# DeMuxRow2.net
KiCad netlist of a schematic drawn in EAGLE
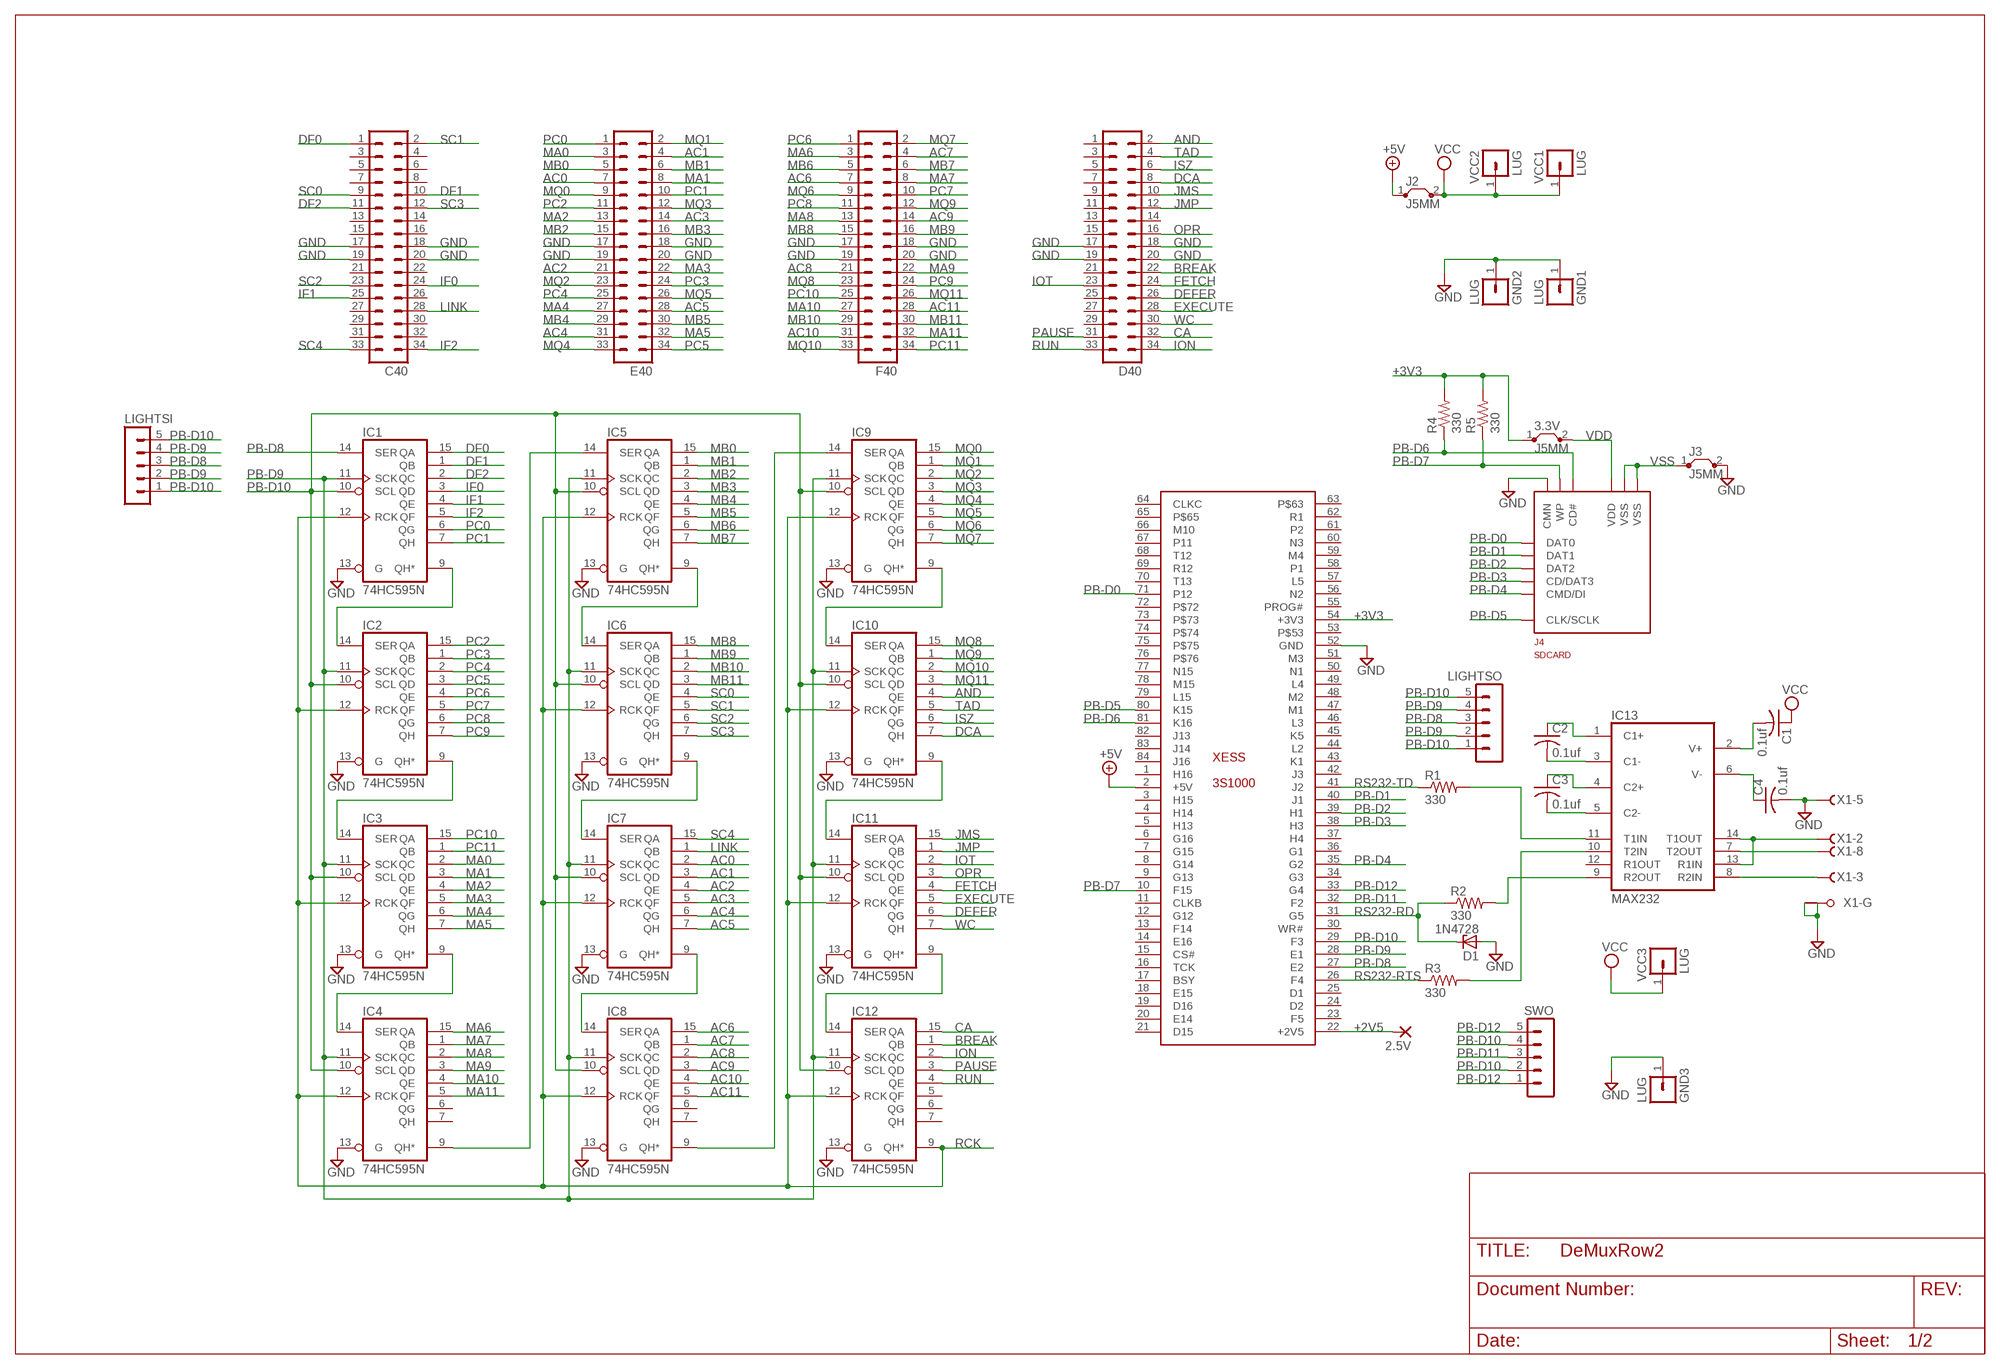
[diagram p0: schematic, sheet 1]
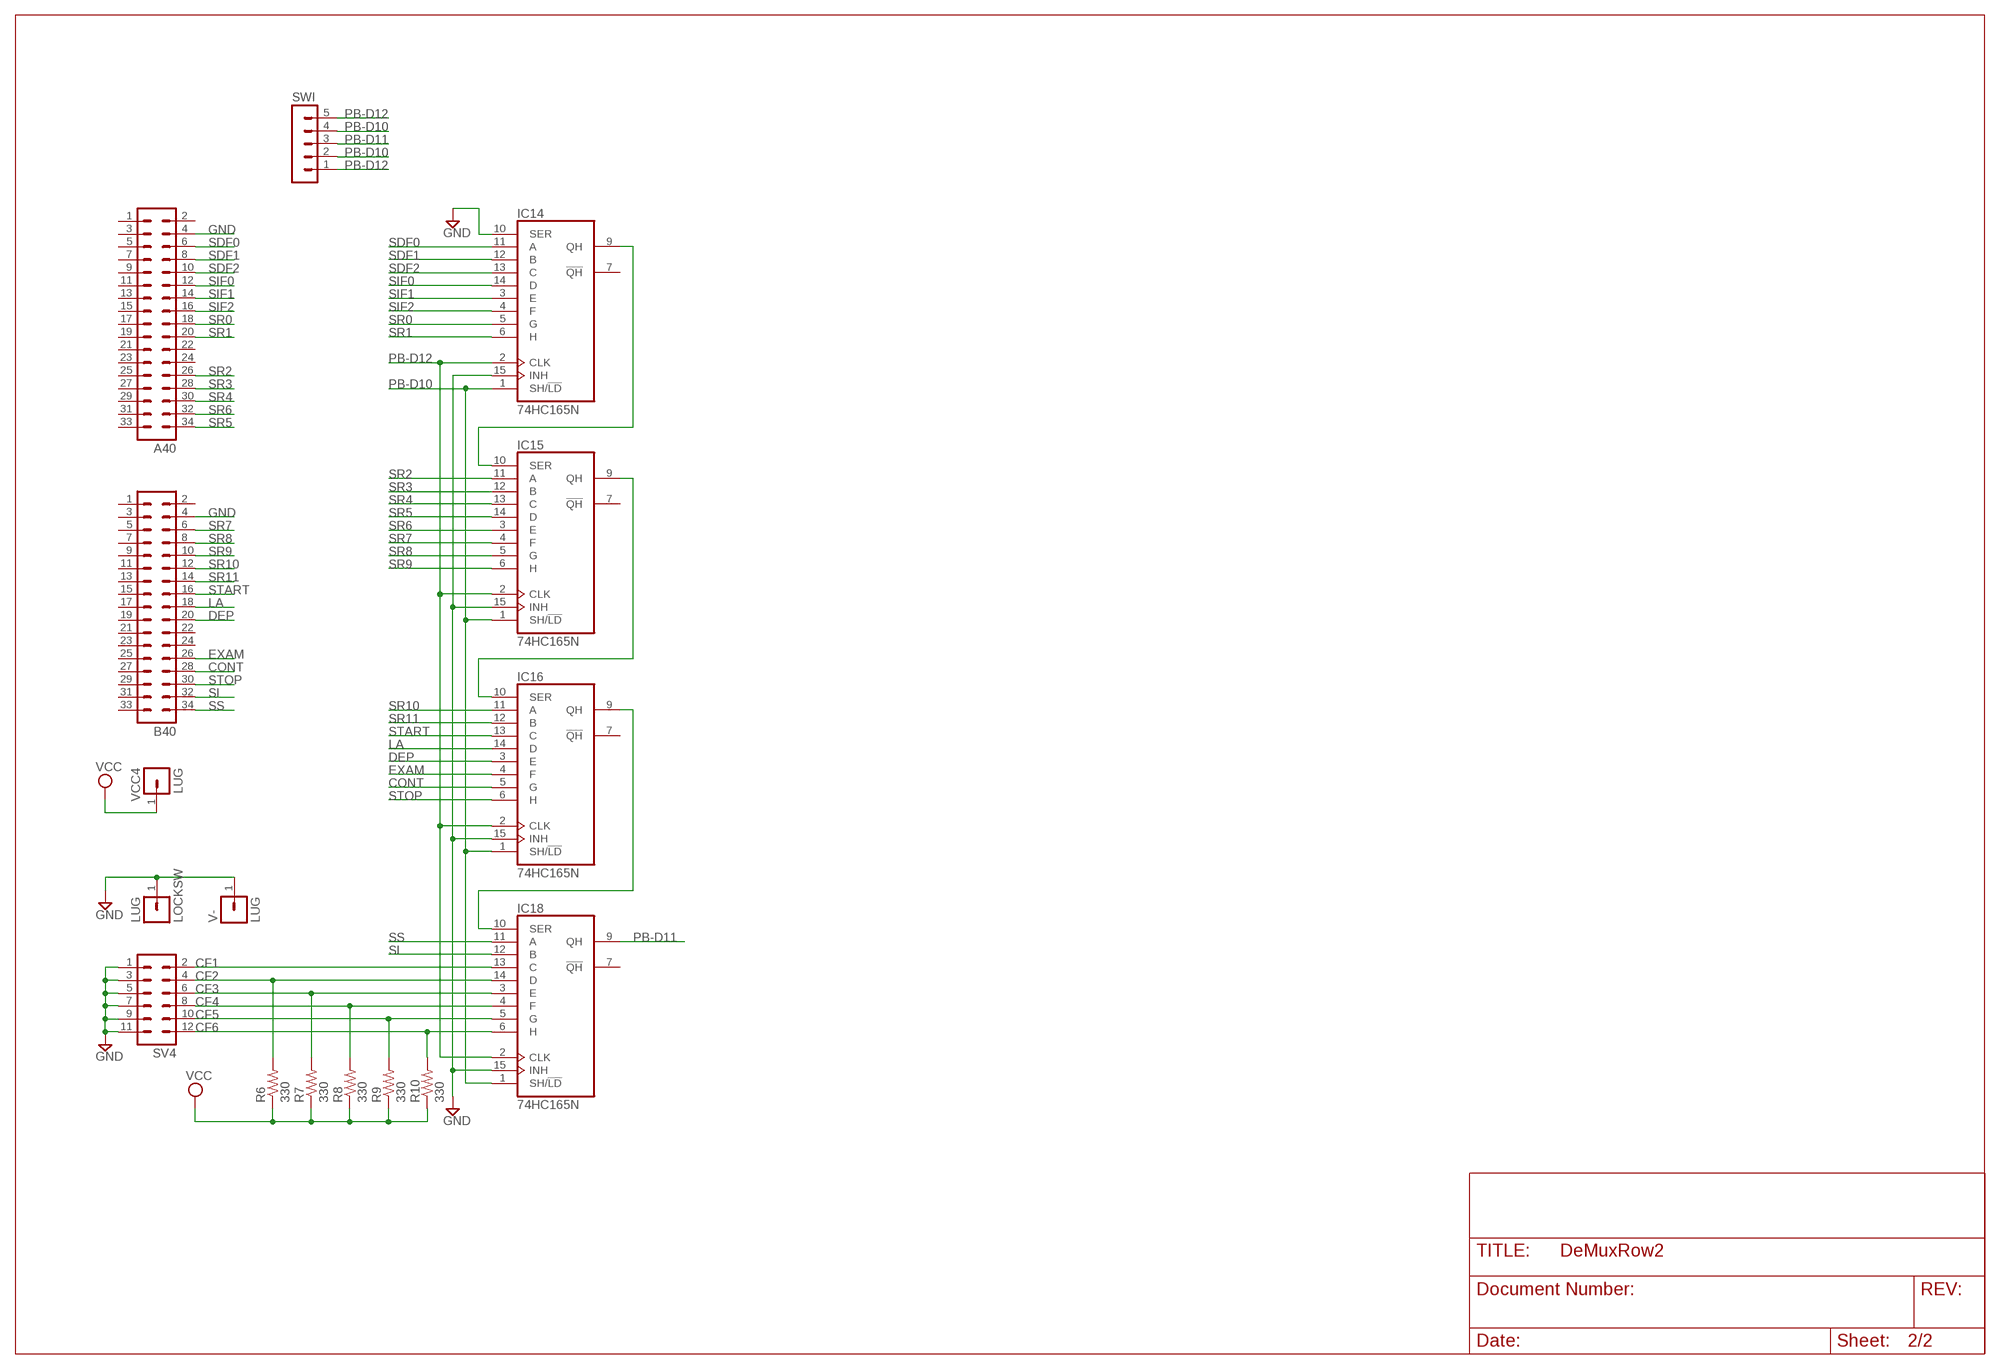
[diagram p1: schematic, sheet 2]

(export (version "E")
  (design (tool "Eeschema 10.0.6"))
  (components
    (comp (ref "A40")
      (value "MA17-2")
      (footprint "eagle-import:MA17-2")
      (libsource (lib "eagle-import") (part "MA17-2"))
    )
    (comp (ref "B40")
      (value "MA17-2")
      (footprint "eagle-import:MA17-2")
      (libsource (lib "eagle-import") (part "MA17-2"))
    )
    (comp (ref "IC14")
      (value "74HC165N")
      (footprint "eagle-import:DIL16")
      (libsource (lib "eagle-import") (part "74165NLS"))
    )
    (comp (ref "IC15")
      (value "74HC165N")
      (footprint "eagle-import:DIL16")
      (libsource (lib "eagle-import") (part "74165NLS"))
    )
    (comp (ref "IC16")
      (value "74HC165N")
      (footprint "eagle-import:DIL16")
      (libsource (lib "eagle-import") (part "74165NLS"))
    )
    (comp (ref "IC18")
      (value "74HC165N")
      (footprint "eagle-import:DIL16")
      (libsource (lib "eagle-import") (part "74165NLS"))
    )
    (comp (ref "LOCKSW")
      (value "LUG")
      (footprint "eagle-import:SPADELUG")
      (libsource (lib "eagle-import") (part "LUG"))
    )
    (comp (ref "R6")
      (value "330")
      (footprint "eagle-import:0207_10")
      (libsource (lib "eagle-import") (part "R-US_0207/10"))
    )
    (comp (ref "R7")
      (value "330")
      (footprint "eagle-import:0207_10")
      (libsource (lib "eagle-import") (part "R-US_0207/10"))
    )
    (comp (ref "R8")
      (value "330")
      (footprint "eagle-import:0207_10")
      (libsource (lib "eagle-import") (part "R-US_0207/10"))
    )
    (comp (ref "R9")
      (value "330")
      (footprint "eagle-import:0207_10")
      (libsource (lib "eagle-import") (part "R-US_0207/10"))
    )
    (comp (ref "R10")
      (value "330")
      (footprint "eagle-import:0207_10")
      (libsource (lib "eagle-import") (part "R-US_0207/10"))
    )
    (comp (ref "SV4")
      (value "MA06-2")
      (footprint "eagle-import:MA06-2")
      (libsource (lib "eagle-import") (part "MA06-2"))
    )
    (comp (ref "SWI")
      (value "MA05-1")
      (footprint "eagle-import:MA05-1")
      (libsource (lib "eagle-import") (part "MA05-1"))
    )
    (comp (ref "V-")
      (value "LUG")
      (footprint "eagle-import:SPADELUG")
      (libsource (lib "eagle-import") (part "LUG"))
    )
    (comp (ref "VCC4")
      (value "LUG")
      (footprint "eagle-import:SPADELUG")
      (libsource (lib "eagle-import") (part "LUG"))
    )
    (comp (ref "2.5V")
      (value "1,6/0,8")
      (footprint "eagle-import:1,6_0,8")
      (libsource (lib "eagle-import") (part "1,6/0,8"))
    )
    (comp (ref "3.3V")
      (value "J5MM")
      (footprint "eagle-import:05")
      (libsource (lib "eagle-import") (part "J5MM"))
    )
    (comp (ref "C1")
      (value "0.1uf")
      (footprint "eagle-import:C050-025X075")
      (libsource (lib "eagle-import") (part "C-US050-025X075"))
    )
    (comp (ref "C2")
      (value "0.1uf")
      (footprint "eagle-import:C050-025X075")
      (libsource (lib "eagle-import") (part "C-US050-025X075"))
    )
    (comp (ref "C3")
      (value "0.1uf")
      (footprint "eagle-import:C050-025X075")
      (libsource (lib "eagle-import") (part "C-US050-025X075"))
    )
    (comp (ref "C4")
      (value "0.1uf")
      (footprint "eagle-import:C050-025X075")
      (libsource (lib "eagle-import") (part "C-US050-025X075"))
    )
    (comp (ref "C40")
      (value "MA17-2")
      (footprint "eagle-import:MA17-2")
      (libsource (lib "eagle-import") (part "MA17-2"))
    )
    (comp (ref "D1")
      (value "1N4728")
      (footprint "eagle-import:DO41Z10")
      (libsource (lib "eagle-import") (part "1N4728"))
    )
    (comp (ref "D40")
      (value "MA17-2")
      (footprint "eagle-import:MA17-2")
      (libsource (lib "eagle-import") (part "MA17-2"))
    )
    (comp (ref "E40")
      (value "MA17-2")
      (footprint "eagle-import:MA17-2")
      (libsource (lib "eagle-import") (part "MA17-2"))
    )
    (comp (ref "F40")
      (value "MA17-2")
      (footprint "eagle-import:MA17-2")
      (libsource (lib "eagle-import") (part "MA17-2"))
    )
    (comp (ref "GND1")
      (value "LUG")
      (footprint "eagle-import:SPADELUG")
      (libsource (lib "eagle-import") (part "LUG"))
    )
    (comp (ref "GND2")
      (value "LUG")
      (footprint "eagle-import:SPADELUG")
      (libsource (lib "eagle-import") (part "LUG"))
    )
    (comp (ref "GND3")
      (value "LUG")
      (footprint "eagle-import:SPADELUG")
      (libsource (lib "eagle-import") (part "LUG"))
    )
    (comp (ref "IC1")
      (value "74HC595N")
      (footprint "eagle-import:DIL16")
      (libsource (lib "eagle-import") (part "74595NLS"))
    )
    (comp (ref "IC2")
      (value "74HC595N")
      (footprint "eagle-import:DIL16")
      (libsource (lib "eagle-import") (part "74595NLS"))
    )
    (comp (ref "IC3")
      (value "74HC595N")
      (footprint "eagle-import:DIL16")
      (libsource (lib "eagle-import") (part "74595NLS"))
    )
    (comp (ref "IC4")
      (value "74HC595N")
      (footprint "eagle-import:DIL16")
      (libsource (lib "eagle-import") (part "74595NLS"))
    )
    (comp (ref "IC5")
      (value "74HC595N")
      (footprint "eagle-import:DIL16")
      (libsource (lib "eagle-import") (part "74595NLS"))
    )
    (comp (ref "IC6")
      (value "74HC595N")
      (footprint "eagle-import:DIL16")
      (libsource (lib "eagle-import") (part "74595NLS"))
    )
    (comp (ref "IC7")
      (value "74HC595N")
      (footprint "eagle-import:DIL16")
      (libsource (lib "eagle-import") (part "74595NLS"))
    )
    (comp (ref "IC8")
      (value "74HC595N")
      (footprint "eagle-import:DIL16")
      (libsource (lib "eagle-import") (part "74595NLS"))
    )
    (comp (ref "IC9")
      (value "74HC595N")
      (footprint "eagle-import:DIL16")
      (libsource (lib "eagle-import") (part "74595NLS"))
    )
    (comp (ref "IC10")
      (value "74HC595N")
      (footprint "eagle-import:DIL16")
      (libsource (lib "eagle-import") (part "74595NLS"))
    )
    (comp (ref "IC11")
      (value "74HC595N")
      (footprint "eagle-import:DIL16")
      (libsource (lib "eagle-import") (part "74595NLS"))
    )
    (comp (ref "IC12")
      (value "74HC595N")
      (footprint "eagle-import:DIL16")
      (libsource (lib "eagle-import") (part "74595NLS"))
    )
    (comp (ref "IC13")
      (value "MAX232")
      (footprint "eagle-import:DIL16")
      (fields (field (name "MF") "MAXIM") (field (name "MPN") "MAX232ACPE+"))
      (libsource (lib "eagle-import") (part "MAX232"))
    )
    (comp (ref "J2")
      (value "J5MM")
      (footprint "eagle-import:05")
      (libsource (lib "eagle-import") (part "J5MM"))
    )
    (comp (ref "J3")
      (value "J5MM")
      (footprint "eagle-import:05")
      (libsource (lib "eagle-import") (part "J5MM"))
    )
    (comp (ref "J4")
      (value "SDCARD")
      (footprint "eagle-import:SCDA5A")
      (libsource (lib "eagle-import") (part "SDCARD"))
    )
    (comp (ref "LIGHTSI")
      (value "MA05-1")
      (footprint "eagle-import:MA05-1")
      (libsource (lib "eagle-import") (part "MA05-1"))
    )
    (comp (ref "LIGHTSO")
      (value "MA05-1")
      (footprint "eagle-import:MA05-1")
      (libsource (lib "eagle-import") (part "MA05-1"))
    )
    (comp (ref "R1")
      (value "330")
      (footprint "eagle-import:0207_10")
      (libsource (lib "eagle-import") (part "R-US_0207/10"))
    )
    (comp (ref "R2")
      (value "330")
      (footprint "eagle-import:0207_10")
      (libsource (lib "eagle-import") (part "R-US_0207/10"))
    )
    (comp (ref "R3")
      (value "330")
      (footprint "eagle-import:0207_10")
      (libsource (lib "eagle-import") (part "R-US_0207/10"))
    )
    (comp (ref "R4")
      (value "330")
      (footprint "eagle-import:0207_10")
      (libsource (lib "eagle-import") (part "R-US_0207/10"))
    )
    (comp (ref "R5")
      (value "330")
      (footprint "eagle-import:0207_10")
      (libsource (lib "eagle-import") (part "R-US_0207/10"))
    )
    (comp (ref "SWO")
      (value "MA05-1")
      (footprint "eagle-import:MA05-1")
      (libsource (lib "eagle-import") (part "MA05-1"))
    )
    (comp (ref "VCC1")
      (value "LUG")
      (footprint "eagle-import:SPADELUG")
      (libsource (lib "eagle-import") (part "LUG"))
    )
    (comp (ref "VCC2")
      (value "LUG")
      (footprint "eagle-import:SPADELUG")
      (libsource (lib "eagle-import") (part "LUG"))
    )
    (comp (ref "VCC3")
      (value "LUG")
      (footprint "eagle-import:SPADELUG")
      (libsource (lib "eagle-import") (part "LUG"))
    )
    (comp (ref "X1")
      (value "F09HPS")
      (footprint "eagle-import:F09HP")
      (libsource (lib "eagle-import") (part "F09HPS"))
    )
    (comp (ref "XESS")
      (value "3S1000")
      (footprint "eagle-import:3S1000")
      (libsource (lib "eagle-import") (part "3S1000"))
    )
  )
  (nets
    (net (code "1") (name "+2V5") (class "Default")
      (node (ref "2.5V") (pin "1") (pinfunction "P_1") (pintype "passive"))
      (node (ref "XESS") (pin "22") (pinfunction "+2V5_22") (pintype "power_in"))
    )
    (net (code "2") (name "+3V3") (class "Default")
      (node (ref "3.3V") (pin "1") (pinfunction "1_1") (pintype "passive"))
      (node (ref "R4") (pin "2") (pinfunction "2_2") (pintype "passive"))
      (node (ref "R5") (pin "2") (pinfunction "2_2") (pintype "passive"))
      (node (ref "XESS") (pin "54") (pinfunction "+3V3_54") (pintype "power_in"))
    )
    (net (code "3") (name "+5V") (class "Default")
      (node (ref "J2") (pin "1") (pinfunction "1_1") (pintype "passive"))
      (node (ref "XESS") (pin "2") (pinfunction "+5V_2") (pintype "power_in"))
    )
    (net (code "4") (name "AC0") (class "Default")
      (node (ref "E40") (pin "7") (pinfunction "7_7") (pintype "passive"))
      (node (ref "IC7") (pin "2") (pinfunction "QC_2") (pintype "tri_state"))
    )
    (net (code "5") (name "AC1") (class "Default")
      (node (ref "E40") (pin "4") (pinfunction "4_4") (pintype "passive"))
      (node (ref "IC7") (pin "3") (pinfunction "QD_3") (pintype "tri_state"))
    )
    (net (code "6") (name "AC2") (class "Default")
      (node (ref "E40") (pin "21") (pinfunction "21_21") (pintype "passive"))
      (node (ref "IC7") (pin "4") (pinfunction "QE_4") (pintype "tri_state"))
    )
    (net (code "7") (name "AC3") (class "Default")
      (node (ref "E40") (pin "14") (pinfunction "14_14") (pintype "passive"))
      (node (ref "IC7") (pin "5") (pinfunction "QF_5") (pintype "tri_state"))
    )
    (net (code "8") (name "AC4") (class "Default")
      (node (ref "E40") (pin "31") (pinfunction "31_31") (pintype "passive"))
      (node (ref "IC7") (pin "6") (pinfunction "QG_6") (pintype "tri_state"))
    )
    (net (code "9") (name "AC5") (class "Default")
      (node (ref "E40") (pin "28") (pinfunction "28_28") (pintype "passive"))
      (node (ref "IC7") (pin "7") (pinfunction "QH_7") (pintype "tri_state"))
    )
    (net (code "10") (name "AC6") (class "Default")
      (node (ref "F40") (pin "7") (pinfunction "7_7") (pintype "passive"))
      (node (ref "IC8") (pin "15") (pinfunction "QA_15") (pintype "tri_state"))
    )
    (net (code "11") (name "AC7") (class "Default")
      (node (ref "F40") (pin "4") (pinfunction "4_4") (pintype "passive"))
      (node (ref "IC8") (pin "1") (pinfunction "QB_1") (pintype "tri_state"))
    )
    (net (code "12") (name "AC8") (class "Default")
      (node (ref "F40") (pin "21") (pinfunction "21_21") (pintype "passive"))
      (node (ref "IC8") (pin "2") (pinfunction "QC_2") (pintype "tri_state"))
    )
    (net (code "13") (name "AC9") (class "Default")
      (node (ref "F40") (pin "14") (pinfunction "14_14") (pintype "passive"))
      (node (ref "IC8") (pin "3") (pinfunction "QD_3") (pintype "tri_state"))
    )
    (net (code "14") (name "AC10") (class "Default")
      (node (ref "F40") (pin "31") (pinfunction "31_31") (pintype "passive"))
      (node (ref "IC8") (pin "4") (pinfunction "QE_4") (pintype "tri_state"))
    )
    (net (code "15") (name "AC11") (class "Default")
      (node (ref "F40") (pin "28") (pinfunction "28_28") (pintype "passive"))
      (node (ref "IC8") (pin "5") (pinfunction "QF_5") (pintype "tri_state"))
    )
    (net (code "16") (name "AND") (class "Default")
      (node (ref "D40") (pin "2") (pinfunction "2_2") (pintype "passive"))
      (node (ref "IC10") (pin "4") (pinfunction "QE_4") (pintype "tri_state"))
    )
    (net (code "17") (name "BREAK") (class "Default")
      (node (ref "D40") (pin "22") (pinfunction "22_22") (pintype "passive"))
      (node (ref "IC12") (pin "1") (pinfunction "QB_1") (pintype "tri_state"))
    )
    (net (code "18") (name "CA") (class "Default")
      (node (ref "D40") (pin "32") (pinfunction "32_32") (pintype "passive"))
      (node (ref "IC12") (pin "15") (pinfunction "QA_15") (pintype "tri_state"))
    )
    (net (code "19") (name "CF1") (class "Default")
      (node (ref "IC18") (pin "13") (pinfunction "C_13") (pintype "input"))
      (node (ref "SV4") (pin "2") (pinfunction "2_2") (pintype "passive"))
    )
    (net (code "20") (name "CF2") (class "Default")
      (node (ref "IC18") (pin "14") (pinfunction "D_14") (pintype "input"))
      (node (ref "R6") (pin "2") (pinfunction "2_2") (pintype "passive"))
      (node (ref "SV4") (pin "4") (pinfunction "4_4") (pintype "passive"))
    )
    (net (code "21") (name "CF3") (class "Default")
      (node (ref "IC18") (pin "3") (pinfunction "E_3") (pintype "input"))
      (node (ref "R7") (pin "2") (pinfunction "2_2") (pintype "passive"))
      (node (ref "SV4") (pin "6") (pinfunction "6_6") (pintype "passive"))
    )
    (net (code "22") (name "CF4") (class "Default")
      (node (ref "IC18") (pin "4") (pinfunction "F_4") (pintype "input"))
      (node (ref "R8") (pin "2") (pinfunction "2_2") (pintype "passive"))
      (node (ref "SV4") (pin "8") (pinfunction "8_8") (pintype "passive"))
    )
    (net (code "23") (name "CF5") (class "Default")
      (node (ref "IC18") (pin "5") (pinfunction "G_5") (pintype "input"))
      (node (ref "R9") (pin "2") (pinfunction "2_2") (pintype "passive"))
      (node (ref "SV4") (pin "10") (pinfunction "10_10") (pintype "passive"))
    )
    (net (code "24") (name "CF6") (class "Default")
      (node (ref "IC18") (pin "6") (pinfunction "H_6") (pintype "input"))
      (node (ref "R10") (pin "2") (pinfunction "2_2") (pintype "passive"))
      (node (ref "SV4") (pin "12") (pinfunction "12_12") (pintype "passive"))
    )
    (net (code "25") (name "CONT") (class "Default")
      (node (ref "B40") (pin "28") (pinfunction "28_28") (pintype "passive"))
      (node (ref "IC16") (pin "5") (pinfunction "G_5") (pintype "input"))
    )
    (net (code "26") (name "DCA") (class "Default")
      (node (ref "D40") (pin "8") (pinfunction "8_8") (pintype "passive"))
      (node (ref "IC10") (pin "7") (pinfunction "QH_7") (pintype "tri_state"))
    )
    (net (code "27") (name "DEFER") (class "Default")
      (node (ref "D40") (pin "26") (pinfunction "26_26") (pintype "passive"))
      (node (ref "IC11") (pin "6") (pinfunction "QG_6") (pintype "tri_state"))
    )
    (net (code "28") (name "DEP") (class "Default")
      (node (ref "B40") (pin "20") (pinfunction "20_20") (pintype "passive"))
      (node (ref "IC16") (pin "3") (pinfunction "E_3") (pintype "input"))
    )
    (net (code "29") (name "DF0") (class "Default")
      (node (ref "C40") (pin "1") (pinfunction "1_1") (pintype "passive"))
      (node (ref "IC1") (pin "15") (pinfunction "QA_15") (pintype "tri_state"))
    )
    (net (code "30") (name "DF1") (class "Default")
      (node (ref "C40") (pin "10") (pinfunction "10_10") (pintype "passive"))
      (node (ref "IC1") (pin "1") (pinfunction "QB_1") (pintype "tri_state"))
    )
    (net (code "31") (name "DF2") (class "Default")
      (node (ref "C40") (pin "11") (pinfunction "11_11") (pintype "passive"))
      (node (ref "IC1") (pin "2") (pinfunction "QC_2") (pintype "tri_state"))
    )
    (net (code "32") (name "EXAM") (class "Default")
      (node (ref "B40") (pin "26") (pinfunction "26_26") (pintype "passive"))
      (node (ref "IC16") (pin "4") (pinfunction "F_4") (pintype "input"))
    )
    (net (code "33") (name "EXECUTE") (class "Default")
      (node (ref "D40") (pin "28") (pinfunction "28_28") (pintype "passive"))
      (node (ref "IC11") (pin "5") (pinfunction "QF_5") (pintype "tri_state"))
    )
    (net (code "34") (name "FETCH") (class "Default")
      (node (ref "D40") (pin "24") (pinfunction "24_24") (pintype "passive"))
      (node (ref "IC11") (pin "4") (pinfunction "QE_4") (pintype "tri_state"))
    )
    (net (code "35") (name "GND") (class "Default")
      (node (ref "A40") (pin "4") (pinfunction "4_4") (pintype "passive"))
      (node (ref "B40") (pin "4") (pinfunction "4_4") (pintype "passive"))
      (node (ref "C4") (pin "2") (pinfunction "2_2") (pintype "passive"))
      (node (ref "C40") (pin "17") (pinfunction "17_17") (pintype "passive"))
      (node (ref "C40") (pin "18") (pinfunction "18_18") (pintype "passive"))
      (node (ref "C40") (pin "19") (pinfunction "19_19") (pintype "passive"))
      (node (ref "C40") (pin "20") (pinfunction "20_20") (pintype "passive"))
      (node (ref "D1") (pin "A") (pinfunction "A_A") (pintype "passive"))
      (node (ref "D40") (pin "17") (pinfunction "17_17") (pintype "passive"))
      (node (ref "D40") (pin "18") (pinfunction "18_18") (pintype "passive"))
      (node (ref "D40") (pin "19") (pinfunction "19_19") (pintype "passive"))
      (node (ref "D40") (pin "20") (pinfunction "20_20") (pintype "passive"))
      (node (ref "E40") (pin "17") (pinfunction "17_17") (pintype "passive"))
      (node (ref "E40") (pin "18") (pinfunction "18_18") (pintype "passive"))
      (node (ref "E40") (pin "19") (pinfunction "19_19") (pintype "passive"))
      (node (ref "E40") (pin "20") (pinfunction "20_20") (pintype "passive"))
      (node (ref "F40") (pin "17") (pinfunction "17_17") (pintype "passive"))
      (node (ref "F40") (pin "18") (pinfunction "18_18") (pintype "passive"))
      (node (ref "F40") (pin "19") (pinfunction "19_19") (pintype "passive"))
      (node (ref "F40") (pin "20") (pinfunction "20_20") (pintype "passive"))
      (node (ref "GND1") (pin "1") (pinfunction "1_1") (pintype "passive"))
      (node (ref "GND2") (pin "1") (pinfunction "1_1") (pintype "passive"))
      (node (ref "GND3") (pin "1") (pinfunction "1_1") (pintype "passive"))
      (node (ref "IC1") (pin "13") (pinfunction "G_13") (pintype "input"))
      (node (ref "IC10") (pin "13") (pinfunction "G_13") (pintype "input"))
      (node (ref "IC11") (pin "13") (pinfunction "G_13") (pintype "input"))
      (node (ref "IC12") (pin "13") (pinfunction "G_13") (pintype "input"))
      (node (ref "IC14") (pin "10") (pinfunction "SER_10") (pintype "input"))
      (node (ref "IC14") (pin "15") (pinfunction "INH_15") (pintype "input"))
      (node (ref "IC15") (pin "15") (pinfunction "INH_15") (pintype "input"))
      (node (ref "IC16") (pin "15") (pinfunction "INH_15") (pintype "input"))
      (node (ref "IC18") (pin "15") (pinfunction "INH_15") (pintype "input"))
      (node (ref "IC2") (pin "13") (pinfunction "G_13") (pintype "input"))
      (node (ref "IC3") (pin "13") (pinfunction "G_13") (pintype "input"))
      (node (ref "IC4") (pin "13") (pinfunction "G_13") (pintype "input"))
      (node (ref "IC5") (pin "13") (pinfunction "G_13") (pintype "input"))
      (node (ref "IC6") (pin "13") (pinfunction "G_13") (pintype "input"))
      (node (ref "IC7") (pin "13") (pinfunction "G_13") (pintype "input"))
      (node (ref "IC8") (pin "13") (pinfunction "G_13") (pintype "input"))
      (node (ref "IC9") (pin "13") (pinfunction "G_13") (pintype "input"))
      (node (ref "J3") (pin "2") (pinfunction "2_2") (pintype "passive"))
      (node (ref "J4") (pin "11") (pinfunction "CMN_11") (pintype "input"))
      (node (ref "LOCKSW") (pin "1") (pinfunction "1_1") (pintype "passive"))
      (node (ref "SV4") (pin "1") (pinfunction "1_1") (pintype "passive"))
      (node (ref "SV4") (pin "11") (pinfunction "11_11") (pintype "passive"))
      (node (ref "SV4") (pin "3") (pinfunction "3_3") (pintype "passive"))
      (node (ref "SV4") (pin "5") (pinfunction "5_5") (pintype "passive"))
      (node (ref "SV4") (pin "7") (pinfunction "7_7") (pintype "passive"))
      (node (ref "SV4") (pin "9") (pinfunction "9_9") (pintype "passive"))
      (node (ref "V-") (pin "1") (pinfunction "1_1") (pintype "passive"))
      (node (ref "X1") (pin "5") (pinfunction "F_5") (pintype "passive"))
      (node (ref "X1") (pin "G1") (pinfunction "G1_G1") (pintype "passive"))
      (node (ref "X1") (pin "G2") (pinfunction "G2_G2") (pintype "passive"))
      (node (ref "XESS") (pin "52") (pinfunction "GND_52") (pintype "power_in"))
    )
    (net (code "36") (name "IF0") (class "Default")
      (node (ref "C40") (pin "24") (pinfunction "24_24") (pintype "passive"))
      (node (ref "IC1") (pin "3") (pinfunction "QD_3") (pintype "tri_state"))
    )
    (net (code "37") (name "IF1") (class "Default")
      (node (ref "C40") (pin "25") (pinfunction "25_25") (pintype "passive"))
      (node (ref "IC1") (pin "4") (pinfunction "QE_4") (pintype "tri_state"))
    )
    (net (code "38") (name "IF2") (class "Default")
      (node (ref "C40") (pin "34") (pinfunction "34_34") (pintype "passive"))
      (node (ref "IC1") (pin "5") (pinfunction "QF_5") (pintype "tri_state"))
    )
    (net (code "39") (name "ION") (class "Default")
      (node (ref "D40") (pin "34") (pinfunction "34_34") (pintype "passive"))
      (node (ref "IC12") (pin "2") (pinfunction "QC_2") (pintype "tri_state"))
    )
    (net (code "40") (name "IOT") (class "Default")
      (node (ref "D40") (pin "23") (pinfunction "23_23") (pintype "passive"))
      (node (ref "IC11") (pin "2") (pinfunction "QC_2") (pintype "tri_state"))
    )
    (net (code "41") (name "ISZ") (class "Default")
      (node (ref "D40") (pin "6") (pinfunction "6_6") (pintype "passive"))
      (node (ref "IC10") (pin "6") (pinfunction "QG_6") (pintype "tri_state"))
    )
    (net (code "42") (name "JMP") (class "Default")
      (node (ref "D40") (pin "12") (pinfunction "12_12") (pintype "passive"))
      (node (ref "IC11") (pin "1") (pinfunction "QB_1") (pintype "tri_state"))
    )
    (net (code "43") (name "JMS") (class "Default")
      (node (ref "D40") (pin "10") (pinfunction "10_10") (pintype "passive"))
      (node (ref "IC11") (pin "15") (pinfunction "QA_15") (pintype "tri_state"))
    )
    (net (code "44") (name "LA") (class "Default")
      (node (ref "B40") (pin "18") (pinfunction "18_18") (pintype "passive"))
      (node (ref "IC16") (pin "14") (pinfunction "D_14") (pintype "input"))
    )
    (net (code "45") (name "LINK") (class "Default")
      (node (ref "C40") (pin "28") (pinfunction "28_28") (pintype "passive"))
      (node (ref "IC7") (pin "1") (pinfunction "QB_1") (pintype "tri_state"))
    )
    (net (code "46") (name "MA0") (class "Default")
      (node (ref "E40") (pin "3") (pinfunction "3_3") (pintype "passive"))
      (node (ref "IC3") (pin "2") (pinfunction "QC_2") (pintype "tri_state"))
    )
    (net (code "47") (name "MA1") (class "Default")
      (node (ref "E40") (pin "8") (pinfunction "8_8") (pintype "passive"))
      (node (ref "IC3") (pin "3") (pinfunction "QD_3") (pintype "tri_state"))
    )
    (net (code "48") (name "MA2") (class "Default")
      (node (ref "E40") (pin "13") (pinfunction "13_13") (pintype "passive"))
      (node (ref "IC3") (pin "4") (pinfunction "QE_4") (pintype "tri_state"))
    )
    (net (code "49") (name "MA3") (class "Default")
      (node (ref "E40") (pin "22") (pinfunction "22_22") (pintype "passive"))
      (node (ref "IC3") (pin "5") (pinfunction "QF_5") (pintype "tri_state"))
    )
    (net (code "50") (name "MA4") (class "Default")
      (node (ref "E40") (pin "27") (pinfunction "27_27") (pintype "passive"))
      (node (ref "IC3") (pin "6") (pinfunction "QG_6") (pintype "tri_state"))
    )
    (net (code "51") (name "MA5") (class "Default")
      (node (ref "E40") (pin "32") (pinfunction "32_32") (pintype "passive"))
      (node (ref "IC3") (pin "7") (pinfunction "QH_7") (pintype "tri_state"))
    )
    (net (code "52") (name "MA6") (class "Default")
      (node (ref "F40") (pin "3") (pinfunction "3_3") (pintype "passive"))
      (node (ref "IC4") (pin "15") (pinfunction "QA_15") (pintype "tri_state"))
    )
    (net (code "53") (name "MA7") (class "Default")
      (node (ref "F40") (pin "8") (pinfunction "8_8") (pintype "passive"))
      (node (ref "IC4") (pin "1") (pinfunction "QB_1") (pintype "tri_state"))
    )
    (net (code "54") (name "MA8") (class "Default")
      (node (ref "F40") (pin "13") (pinfunction "13_13") (pintype "passive"))
      (node (ref "IC4") (pin "2") (pinfunction "QC_2") (pintype "tri_state"))
    )
    (net (code "55") (name "MA9") (class "Default")
      (node (ref "F40") (pin "22") (pinfunction "22_22") (pintype "passive"))
      (node (ref "IC4") (pin "3") (pinfunction "QD_3") (pintype "tri_state"))
    )
    (net (code "56") (name "MA10") (class "Default")
      (node (ref "F40") (pin "27") (pinfunction "27_27") (pintype "passive"))
      (node (ref "IC4") (pin "4") (pinfunction "QE_4") (pintype "tri_state"))
    )
    (net (code "57") (name "MA11") (class "Default")
      (node (ref "F40") (pin "32") (pinfunction "32_32") (pintype "passive"))
      (node (ref "IC4") (pin "5") (pinfunction "QF_5") (pintype "tri_state"))
    )
    (net (code "58") (name "MB0") (class "Default")
      (node (ref "E40") (pin "5") (pinfunction "5_5") (pintype "passive"))
      (node (ref "IC5") (pin "15") (pinfunction "QA_15") (pintype "tri_state"))
    )
    (net (code "59") (name "MB1") (class "Default")
      (node (ref "E40") (pin "6") (pinfunction "6_6") (pintype "passive"))
      (node (ref "IC5") (pin "1") (pinfunction "QB_1") (pintype "tri_state"))
    )
    (net (code "60") (name "MB2") (class "Default")
      (node (ref "E40") (pin "15") (pinfunction "15_15") (pintype "passive"))
      (node (ref "IC5") (pin "2") (pinfunction "QC_2") (pintype "tri_state"))
    )
    (net (code "61") (name "MB3") (class "Default")
      (node (ref "E40") (pin "16") (pinfunction "16_16") (pintype "passive"))
      (node (ref "IC5") (pin "3") (pinfunction "QD_3") (pintype "tri_state"))
    )
    (net (code "62") (name "MB4") (class "Default")
      (node (ref "E40") (pin "29") (pinfunction "29_29") (pintype "passive"))
      (node (ref "IC5") (pin "4") (pinfunction "QE_4") (pintype "tri_state"))
    )
    (net (code "63") (name "MB5") (class "Default")
      (node (ref "E40") (pin "30") (pinfunction "30_30") (pintype "passive"))
      (node (ref "IC5") (pin "5") (pinfunction "QF_5") (pintype "tri_state"))
    )
    (net (code "64") (name "MB6") (class "Default")
      (node (ref "F40") (pin "5") (pinfunction "5_5") (pintype "passive"))
      (node (ref "IC5") (pin "6") (pinfunction "QG_6") (pintype "tri_state"))
    )
    (net (code "65") (name "MB7") (class "Default")
      (node (ref "F40") (pin "6") (pinfunction "6_6") (pintype "passive"))
      (node (ref "IC5") (pin "7") (pinfunction "QH_7") (pintype "tri_state"))
    )
    (net (code "66") (name "MB8") (class "Default")
      (node (ref "F40") (pin "15") (pinfunction "15_15") (pintype "passive"))
      (node (ref "IC6") (pin "15") (pinfunction "QA_15") (pintype "tri_state"))
    )
    (net (code "67") (name "MB9") (class "Default")
      (node (ref "F40") (pin "16") (pinfunction "16_16") (pintype "passive"))
      (node (ref "IC6") (pin "1") (pinfunction "QB_1") (pintype "tri_state"))
    )
    (net (code "68") (name "MB10") (class "Default")
      (node (ref "F40") (pin "29") (pinfunction "29_29") (pintype "passive"))
      (node (ref "IC6") (pin "2") (pinfunction "QC_2") (pintype "tri_state"))
    )
    (net (code "69") (name "MB11") (class "Default")
      (node (ref "F40") (pin "30") (pinfunction "30_30") (pintype "passive"))
      (node (ref "IC6") (pin "3") (pinfunction "QD_3") (pintype "tri_state"))
    )
    (net (code "70") (name "MQ0") (class "Default")
      (node (ref "E40") (pin "9") (pinfunction "9_9") (pintype "passive"))
      (node (ref "IC9") (pin "15") (pinfunction "QA_15") (pintype "tri_state"))
    )
    (net (code "71") (name "MQ1") (class "Default")
      (node (ref "E40") (pin "2") (pinfunction "2_2") (pintype "passive"))
      (node (ref "IC9") (pin "1") (pinfunction "QB_1") (pintype "tri_state"))
    )
    (net (code "72") (name "MQ2") (class "Default")
      (node (ref "E40") (pin "23") (pinfunction "23_23") (pintype "passive"))
      (node (ref "IC9") (pin "2") (pinfunction "QC_2") (pintype "tri_state"))
    )
    (net (code "73") (name "MQ3") (class "Default")
      (node (ref "E40") (pin "12") (pinfunction "12_12") (pintype "passive"))
      (node (ref "IC9") (pin "3") (pinfunction "QD_3") (pintype "tri_state"))
    )
    (net (code "74") (name "MQ4") (class "Default")
      (node (ref "E40") (pin "33") (pinfunction "33_33") (pintype "passive"))
      (node (ref "IC9") (pin "4") (pinfunction "QE_4") (pintype "tri_state"))
    )
    (net (code "75") (name "MQ5") (class "Default")
      (node (ref "E40") (pin "26") (pinfunction "26_26") (pintype "passive"))
      (node (ref "IC9") (pin "5") (pinfunction "QF_5") (pintype "tri_state"))
    )
    (net (code "76") (name "MQ6") (class "Default")
      (node (ref "F40") (pin "9") (pinfunction "9_9") (pintype "passive"))
      (node (ref "IC9") (pin "6") (pinfunction "QG_6") (pintype "tri_state"))
    )
    (net (code "77") (name "MQ7") (class "Default")
      (node (ref "F40") (pin "2") (pinfunction "2_2") (pintype "passive"))
      (node (ref "IC9") (pin "7") (pinfunction "QH_7") (pintype "tri_state"))
    )
    (net (code "78") (name "MQ8") (class "Default")
      (node (ref "F40") (pin "23") (pinfunction "23_23") (pintype "passive"))
      (node (ref "IC10") (pin "15") (pinfunction "QA_15") (pintype "tri_state"))
    )
    (net (code "79") (name "MQ9") (class "Default")
      (node (ref "F40") (pin "12") (pinfunction "12_12") (pintype "passive"))
      (node (ref "IC10") (pin "1") (pinfunction "QB_1") (pintype "tri_state"))
    )
    (net (code "80") (name "MQ10") (class "Default")
      (node (ref "F40") (pin "33") (pinfunction "33_33") (pintype "passive"))
      (node (ref "IC10") (pin "2") (pinfunction "QC_2") (pintype "tri_state"))
    )
    (net (code "81") (name "MQ11") (class "Default")
      (node (ref "F40") (pin "26") (pinfunction "26_26") (pintype "passive"))
      (node (ref "IC10") (pin "3") (pinfunction "QD_3") (pintype "tri_state"))
    )
    (net (code "82") (name "Net-(IC1A-QH*)") (class "Default")
      (node (ref "IC1") (pin "9") (pinfunction "QH*_9") (pintype "tri_state"))
      (node (ref "IC2") (pin "14") (pinfunction "SER_14") (pintype "input"))
    )
    (net (code "83") (name "Net-(IC2A-QH*)") (class "Default")
      (node (ref "IC2") (pin "9") (pinfunction "QH*_9") (pintype "tri_state"))
      (node (ref "IC3") (pin "14") (pinfunction "SER_14") (pintype "input"))
    )
    (net (code "84") (name "Net-(IC3A-QH*)") (class "Default")
      (node (ref "IC3") (pin "9") (pinfunction "QH*_9") (pintype "tri_state"))
      (node (ref "IC4") (pin "14") (pinfunction "SER_14") (pintype "input"))
    )
    (net (code "85") (name "Net-(IC4A-QH*)") (class "Default")
      (node (ref "IC4") (pin "9") (pinfunction "QH*_9") (pintype "tri_state"))
      (node (ref "IC5") (pin "14") (pinfunction "SER_14") (pintype "input"))
    )
    (net (code "86") (name "Net-(IC5A-QH*)") (class "Default")
      (node (ref "IC5") (pin "9") (pinfunction "QH*_9") (pintype "tri_state"))
      (node (ref "IC6") (pin "14") (pinfunction "SER_14") (pintype "input"))
    )
    (net (code "87") (name "Net-(IC6A-QH*)") (class "Default")
      (node (ref "IC6") (pin "9") (pinfunction "QH*_9") (pintype "tri_state"))
      (node (ref "IC7") (pin "14") (pinfunction "SER_14") (pintype "input"))
    )
    (net (code "88") (name "Net-(IC7A-QH*)") (class "Default")
      (node (ref "IC7") (pin "9") (pinfunction "QH*_9") (pintype "tri_state"))
      (node (ref "IC8") (pin "14") (pinfunction "SER_14") (pintype "input"))
    )
    (net (code "89") (name "Net-(IC8A-QH*)") (class "Default")
      (node (ref "IC8") (pin "9") (pinfunction "QH*_9") (pintype "tri_state"))
      (node (ref "IC9") (pin "14") (pinfunction "SER_14") (pintype "input"))
    )
    (net (code "90") (name "Net-(IC10A-QH*)") (class "Default")
      (node (ref "IC10") (pin "9") (pinfunction "QH*_9") (pintype "tri_state"))
      (node (ref "IC11") (pin "14") (pinfunction "SER_14") (pintype "input"))
    )
    (net (code "91") (name "Net-(IC10A-SER)") (class "Default")
      (node (ref "IC10") (pin "14") (pinfunction "SER_14") (pintype "input"))
      (node (ref "IC9") (pin "9") (pinfunction "QH*_9") (pintype "tri_state"))
    )
    (net (code "92") (name "Net-(IC11A-QH*)") (class "Default")
      (node (ref "IC11") (pin "9") (pinfunction "QH*_9") (pintype "tri_state"))
      (node (ref "IC12") (pin "14") (pinfunction "SER_14") (pintype "input"))
    )
    (net (code "93") (name "Net-(IC13A-C1+)") (class "Default")
      (node (ref "C2") (pin "1") (pinfunction "1_1") (pintype "passive"))
      (node (ref "IC13") (pin "1") (pinfunction "C1+_1") (pintype "bidirectional"))
    )
    (net (code "94") (name "Net-(IC13A-C1-)") (class "Default")
      (node (ref "C2") (pin "2") (pinfunction "2_2") (pintype "passive"))
      (node (ref "IC13") (pin "3") (pinfunction "C1-_3") (pintype "bidirectional"))
    )
    (net (code "95") (name "Net-(IC13A-C2+)") (class "Default")
      (node (ref "C3") (pin "1") (pinfunction "1_1") (pintype "passive"))
      (node (ref "IC13") (pin "4") (pinfunction "C2+_4") (pintype "bidirectional"))
    )
    (net (code "96") (name "Net-(IC13A-C2-)") (class "Default")
      (node (ref "C3") (pin "2") (pinfunction "2_2") (pintype "passive"))
      (node (ref "IC13") (pin "5") (pinfunction "C2-_5") (pintype "bidirectional"))
    )
    (net (code "97") (name "Net-(IC13A-R1IN)") (class "Default")
      (node (ref "IC13") (pin "13") (pinfunction "R1IN_13") (pintype "input"))
      (node (ref "IC13") (pin "14") (pinfunction "T1OUT_14") (pintype "output"))
      (node (ref "X1") (pin "2") (pinfunction "F_2") (pintype "passive"))
    )
    (net (code "98") (name "Net-(IC13A-R2IN)") (class "Default")
      (node (ref "IC13") (pin "8") (pinfunction "R2IN_8") (pintype "input"))
      (node (ref "X1") (pin "3") (pinfunction "F_3") (pintype "passive"))
    )
    (net (code "99") (name "Net-(IC13A-R2OUT)") (class "Default")
      (node (ref "IC13") (pin "9") (pinfunction "R2OUT_9") (pintype "output"))
      (node (ref "R2") (pin "2") (pinfunction "2_2") (pintype "passive"))
    )
    (net (code "100") (name "Net-(IC13A-T1IN)") (class "Default")
      (node (ref "IC13") (pin "11") (pinfunction "T1IN_11") (pintype "input"))
      (node (ref "R1") (pin "2") (pinfunction "2_2") (pintype "passive"))
    )
    (net (code "101") (name "Net-(IC13A-T2IN)") (class "Default")
      (node (ref "IC13") (pin "10") (pinfunction "T2IN_10") (pintype "input"))
      (node (ref "R3") (pin "2") (pinfunction "2_2") (pintype "passive"))
    )
    (net (code "102") (name "Net-(IC13A-T2OUT)") (class "Default")
      (node (ref "IC13") (pin "7") (pinfunction "T2OUT_7") (pintype "output"))
      (node (ref "X1") (pin "8") (pinfunction "F_8") (pintype "passive"))
    )
    (net (code "103") (name "Net-(IC13A-V+)") (class "Default")
      (node (ref "C1") (pin "2") (pinfunction "2_2") (pintype "passive"))
      (node (ref "IC13") (pin "2") (pinfunction "V+_2") (pintype "bidirectional"))
    )
    (net (code "104") (name "Net-(IC13A-V-)") (class "Default")
      (node (ref "C4") (pin "1") (pinfunction "1_1") (pintype "passive"))
      (node (ref "IC13") (pin "6") (pinfunction "V-_6") (pintype "bidirectional"))
    )
    (net (code "105") (name "Net-(IC14A-QH)") (class "Default")
      (node (ref "IC14") (pin "9") (pinfunction "QH_9") (pintype "output"))
      (node (ref "IC15") (pin "10") (pinfunction "SER_10") (pintype "input"))
    )
    (net (code "106") (name "Net-(IC15A-QH)") (class "Default")
      (node (ref "IC15") (pin "9") (pinfunction "QH_9") (pintype "output"))
      (node (ref "IC16") (pin "10") (pinfunction "SER_10") (pintype "input"))
    )
    (net (code "107") (name "Net-(IC16A-QH)") (class "Default")
      (node (ref "IC16") (pin "9") (pinfunction "QH_9") (pintype "output"))
      (node (ref "IC18") (pin "10") (pinfunction "SER_10") (pintype "input"))
    )
    (net (code "108") (name "OPR") (class "Default")
      (node (ref "D40") (pin "16") (pinfunction "16_16") (pintype "passive"))
      (node (ref "IC11") (pin "3") (pinfunction "QD_3") (pintype "tri_state"))
    )
    (net (code "109") (name "PAUSE") (class "Default")
      (node (ref "D40") (pin "31") (pinfunction "31_31") (pintype "passive"))
      (node (ref "IC12") (pin "3") (pinfunction "QD_3") (pintype "tri_state"))
    )
    (net (code "110") (name "PB-D0") (class "Default")
      (node (ref "J4") (pin "7") (pinfunction "DAT0_7") (pintype "bidirectional"))
      (node (ref "XESS") (pin "71") (pinfunction "P12_71") (pintype "bidirectional"))
    )
    (net (code "111") (name "PB-D1") (class "Default")
      (node (ref "J4") (pin "8") (pinfunction "DAT1_8") (pintype "bidirectional"))
      (node (ref "XESS") (pin "40") (pinfunction "J1_40") (pintype "bidirectional"))
    )
    (net (code "112") (name "PB-D2") (class "Default")
      (node (ref "J4") (pin "9") (pinfunction "DAT2_9") (pintype "bidirectional"))
      (node (ref "XESS") (pin "39") (pinfunction "H1_39") (pintype "bidirectional"))
    )
    (net (code "113") (name "PB-D3") (class "Default")
      (node (ref "J4") (pin "1") (pinfunction "CD/DAT3_1") (pintype "bidirectional"))
      (node (ref "XESS") (pin "38") (pinfunction "H3_38") (pintype "bidirectional"))
    )
    (net (code "114") (name "PB-D4") (class "Default")
      (node (ref "J4") (pin "2") (pinfunction "CMD/DI_2") (pintype "bidirectional"))
      (node (ref "XESS") (pin "35") (pinfunction "G2_35") (pintype "bidirectional"))
    )
    (net (code "115") (name "PB-D5") (class "Default")
      (node (ref "J4") (pin "5") (pinfunction "CLK/SCLK_5") (pintype "bidirectional"))
      (node (ref "XESS") (pin "80") (pinfunction "K15_80") (pintype "bidirectional"))
    )
    (net (code "116") (name "PB-D6") (class "Default")
      (node (ref "J4") (pin "10") (pinfunction "CD#_10") (pintype "output"))
      (node (ref "R4") (pin "1") (pinfunction "1_1") (pintype "passive"))
      (node (ref "XESS") (pin "81") (pinfunction "K16_81") (pintype "bidirectional"))
    )
    (net (code "117") (name "PB-D7") (class "Default")
      (node (ref "J4") (pin "12") (pinfunction "WP_12") (pintype "output"))
      (node (ref "R5") (pin "1") (pinfunction "1_1") (pintype "passive"))
      (node (ref "XESS") (pin "10") (pinfunction "F15_10") (pintype "bidirectional"))
    )
    (net (code "118") (name "PB-D8") (class "Default")
      (node (ref "IC1") (pin "14") (pinfunction "SER_14") (pintype "input"))
      (node (ref "LIGHTSI") (pin "3") (pinfunction "3_3") (pintype "passive"))
      (node (ref "LIGHTSO") (pin "3") (pinfunction "3_3") (pintype "passive"))
      (node (ref "XESS") (pin "27") (pinfunction "E2_27") (pintype "bidirectional"))
    )
    (net (code "119") (name "PB-D9") (class "Default")
      (node (ref "IC1") (pin "11") (pinfunction "SCK_11") (pintype "input"))
      (node (ref "IC10") (pin "11") (pinfunction "SCK_11") (pintype "input"))
      (node (ref "IC11") (pin "11") (pinfunction "SCK_11") (pintype "input"))
      (node (ref "IC12") (pin "11") (pinfunction "SCK_11") (pintype "input"))
      (node (ref "IC2") (pin "11") (pinfunction "SCK_11") (pintype "input"))
      (node (ref "IC3") (pin "11") (pinfunction "SCK_11") (pintype "input"))
      (node (ref "IC4") (pin "11") (pinfunction "SCK_11") (pintype "input"))
      (node (ref "IC5") (pin "11") (pinfunction "SCK_11") (pintype "input"))
      (node (ref "IC6") (pin "11") (pinfunction "SCK_11") (pintype "input"))
      (node (ref "IC7") (pin "11") (pinfunction "SCK_11") (pintype "input"))
      (node (ref "IC8") (pin "11") (pinfunction "SCK_11") (pintype "input"))
      (node (ref "IC9") (pin "11") (pinfunction "SCK_11") (pintype "input"))
      (node (ref "LIGHTSI") (pin "2") (pinfunction "2_2") (pintype "passive"))
      (node (ref "LIGHTSI") (pin "4") (pinfunction "4_4") (pintype "passive"))
      (node (ref "LIGHTSO") (pin "2") (pinfunction "2_2") (pintype "passive"))
      (node (ref "LIGHTSO") (pin "4") (pinfunction "4_4") (pintype "passive"))
      (node (ref "XESS") (pin "28") (pinfunction "E1_28") (pintype "bidirectional"))
    )
    (net (code "120") (name "PB-D10") (class "Default")
      (node (ref "IC1") (pin "10") (pinfunction "SCL_10") (pintype "input"))
      (node (ref "IC10") (pin "10") (pinfunction "SCL_10") (pintype "input"))
      (node (ref "IC11") (pin "10") (pinfunction "SCL_10") (pintype "input"))
      (node (ref "IC12") (pin "10") (pinfunction "SCL_10") (pintype "input"))
      (node (ref "IC14") (pin "1") (pinfunction "SH/~{LD}_1") (pintype "input"))
      (node (ref "IC15") (pin "1") (pinfunction "SH/~{LD}_1") (pintype "input"))
      (node (ref "IC16") (pin "1") (pinfunction "SH/~{LD}_1") (pintype "input"))
      (node (ref "IC18") (pin "1") (pinfunction "SH/~{LD}_1") (pintype "input"))
      (node (ref "IC2") (pin "10") (pinfunction "SCL_10") (pintype "input"))
      (node (ref "IC3") (pin "10") (pinfunction "SCL_10") (pintype "input"))
      (node (ref "IC4") (pin "10") (pinfunction "SCL_10") (pintype "input"))
      (node (ref "IC5") (pin "10") (pinfunction "SCL_10") (pintype "input"))
      (node (ref "IC6") (pin "10") (pinfunction "SCL_10") (pintype "input"))
      (node (ref "IC7") (pin "10") (pinfunction "SCL_10") (pintype "input"))
      (node (ref "IC8") (pin "10") (pinfunction "SCL_10") (pintype "input"))
      (node (ref "IC9") (pin "10") (pinfunction "SCL_10") (pintype "input"))
      (node (ref "LIGHTSI") (pin "1") (pinfunction "1_1") (pintype "passive"))
      (node (ref "LIGHTSI") (pin "5") (pinfunction "5_5") (pintype "passive"))
      (node (ref "LIGHTSO") (pin "1") (pinfunction "1_1") (pintype "passive"))
      (node (ref "LIGHTSO") (pin "5") (pinfunction "5_5") (pintype "passive"))
      (node (ref "SWI") (pin "2") (pinfunction "2_2") (pintype "passive"))
      (node (ref "SWI") (pin "4") (pinfunction "4_4") (pintype "passive"))
      (node (ref "SWO") (pin "2") (pinfunction "2_2") (pintype "passive"))
      (node (ref "SWO") (pin "4") (pinfunction "4_4") (pintype "passive"))
      (node (ref "XESS") (pin "29") (pinfunction "F3_29") (pintype "bidirectional"))
    )
    (net (code "121") (name "PB-D11") (class "Default")
      (node (ref "IC18") (pin "9") (pinfunction "QH_9") (pintype "output"))
      (node (ref "SWI") (pin "3") (pinfunction "3_3") (pintype "passive"))
      (node (ref "SWO") (pin "3") (pinfunction "3_3") (pintype "passive"))
      (node (ref "XESS") (pin "32") (pinfunction "F2_32") (pintype "bidirectional"))
    )
    (net (code "122") (name "PB-D12") (class "Default")
      (node (ref "IC14") (pin "2") (pinfunction "CLK_2") (pintype "input"))
      (node (ref "IC15") (pin "2") (pinfunction "CLK_2") (pintype "input"))
      (node (ref "IC16") (pin "2") (pinfunction "CLK_2") (pintype "input"))
      (node (ref "IC18") (pin "2") (pinfunction "CLK_2") (pintype "input"))
      (node (ref "SWI") (pin "1") (pinfunction "1_1") (pintype "passive"))
      (node (ref "SWI") (pin "5") (pinfunction "5_5") (pintype "passive"))
      (node (ref "SWO") (pin "1") (pinfunction "1_1") (pintype "passive"))
      (node (ref "SWO") (pin "5") (pinfunction "5_5") (pintype "passive"))
      (node (ref "XESS") (pin "33") (pinfunction "G4_33") (pintype "bidirectional"))
    )
    (net (code "123") (name "PC0") (class "Default")
      (node (ref "E40") (pin "1") (pinfunction "1_1") (pintype "passive"))
      (node (ref "IC1") (pin "6") (pinfunction "QG_6") (pintype "tri_state"))
    )
    (net (code "124") (name "PC1") (class "Default")
      (node (ref "E40") (pin "10") (pinfunction "10_10") (pintype "passive"))
      (node (ref "IC1") (pin "7") (pinfunction "QH_7") (pintype "tri_state"))
    )
    (net (code "125") (name "PC2") (class "Default")
      (node (ref "E40") (pin "11") (pinfunction "11_11") (pintype "passive"))
      (node (ref "IC2") (pin "15") (pinfunction "QA_15") (pintype "tri_state"))
    )
    (net (code "126") (name "PC3") (class "Default")
      (node (ref "E40") (pin "24") (pinfunction "24_24") (pintype "passive"))
      (node (ref "IC2") (pin "1") (pinfunction "QB_1") (pintype "tri_state"))
    )
    (net (code "127") (name "PC4") (class "Default")
      (node (ref "E40") (pin "25") (pinfunction "25_25") (pintype "passive"))
      (node (ref "IC2") (pin "2") (pinfunction "QC_2") (pintype "tri_state"))
    )
    (net (code "128") (name "PC5") (class "Default")
      (node (ref "E40") (pin "34") (pinfunction "34_34") (pintype "passive"))
      (node (ref "IC2") (pin "3") (pinfunction "QD_3") (pintype "tri_state"))
    )
    (net (code "129") (name "PC6") (class "Default")
      (node (ref "F40") (pin "1") (pinfunction "1_1") (pintype "passive"))
      (node (ref "IC2") (pin "4") (pinfunction "QE_4") (pintype "tri_state"))
    )
    (net (code "130") (name "PC7") (class "Default")
      (node (ref "F40") (pin "10") (pinfunction "10_10") (pintype "passive"))
      (node (ref "IC2") (pin "5") (pinfunction "QF_5") (pintype "tri_state"))
    )
    (net (code "131") (name "PC8") (class "Default")
      (node (ref "F40") (pin "11") (pinfunction "11_11") (pintype "passive"))
      (node (ref "IC2") (pin "6") (pinfunction "QG_6") (pintype "tri_state"))
    )
    (net (code "132") (name "PC9") (class "Default")
      (node (ref "F40") (pin "24") (pinfunction "24_24") (pintype "passive"))
      (node (ref "IC2") (pin "7") (pinfunction "QH_7") (pintype "tri_state"))
    )
    (net (code "133") (name "PC10") (class "Default")
      (node (ref "F40") (pin "25") (pinfunction "25_25") (pintype "passive"))
      (node (ref "IC3") (pin "15") (pinfunction "QA_15") (pintype "tri_state"))
    )
    (net (code "134") (name "PC11") (class "Default")
      (node (ref "F40") (pin "34") (pinfunction "34_34") (pintype "passive"))
      (node (ref "IC3") (pin "1") (pinfunction "QB_1") (pintype "tri_state"))
    )
    (net (code "135") (name "RCK") (class "Default")
      (node (ref "IC1") (pin "12") (pinfunction "RCK_12") (pintype "input"))
      (node (ref "IC10") (pin "12") (pinfunction "RCK_12") (pintype "input"))
      (node (ref "IC11") (pin "12") (pinfunction "RCK_12") (pintype "input"))
      (node (ref "IC12") (pin "12") (pinfunction "RCK_12") (pintype "input"))
      (node (ref "IC12") (pin "9") (pinfunction "QH*_9") (pintype "tri_state"))
      (node (ref "IC2") (pin "12") (pinfunction "RCK_12") (pintype "input"))
      (node (ref "IC3") (pin "12") (pinfunction "RCK_12") (pintype "input"))
      (node (ref "IC4") (pin "12") (pinfunction "RCK_12") (pintype "input"))
      (node (ref "IC5") (pin "12") (pinfunction "RCK_12") (pintype "input"))
      (node (ref "IC6") (pin "12") (pinfunction "RCK_12") (pintype "input"))
      (node (ref "IC7") (pin "12") (pinfunction "RCK_12") (pintype "input"))
      (node (ref "IC8") (pin "12") (pinfunction "RCK_12") (pintype "input"))
      (node (ref "IC9") (pin "12") (pinfunction "RCK_12") (pintype "input"))
    )
    (net (code "136") (name "RS232-RD") (class "Default")
      (node (ref "D1") (pin "C") (pinfunction "C_C") (pintype "passive"))
      (node (ref "R2") (pin "1") (pinfunction "1_1") (pintype "passive"))
      (node (ref "XESS") (pin "31") (pinfunction "G5_31") (pintype "bidirectional"))
    )
    (net (code "137") (name "RS232-RTS") (class "Default")
      (node (ref "R3") (pin "1") (pinfunction "1_1") (pintype "passive"))
      (node (ref "XESS") (pin "26") (pinfunction "F4_26") (pintype "bidirectional"))
    )
    (net (code "138") (name "RS232-TD") (class "Default")
      (node (ref "R1") (pin "1") (pinfunction "1_1") (pintype "passive"))
      (node (ref "XESS") (pin "41") (pinfunction "J2_41") (pintype "bidirectional"))
    )
    (net (code "139") (name "RUN") (class "Default")
      (node (ref "D40") (pin "33") (pinfunction "33_33") (pintype "passive"))
      (node (ref "IC12") (pin "4") (pinfunction "QE_4") (pintype "tri_state"))
    )
    (net (code "140") (name "SC0") (class "Default")
      (node (ref "C40") (pin "9") (pinfunction "9_9") (pintype "passive"))
      (node (ref "IC6") (pin "4") (pinfunction "QE_4") (pintype "tri_state"))
    )
    (net (code "141") (name "SC1") (class "Default")
      (node (ref "C40") (pin "2") (pinfunction "2_2") (pintype "passive"))
      (node (ref "IC6") (pin "5") (pinfunction "QF_5") (pintype "tri_state"))
    )
    (net (code "142") (name "SC2") (class "Default")
      (node (ref "C40") (pin "23") (pinfunction "23_23") (pintype "passive"))
      (node (ref "IC6") (pin "6") (pinfunction "QG_6") (pintype "tri_state"))
    )
    (net (code "143") (name "SC3") (class "Default")
      (node (ref "C40") (pin "12") (pinfunction "12_12") (pintype "passive"))
      (node (ref "IC6") (pin "7") (pinfunction "QH_7") (pintype "tri_state"))
    )
    (net (code "144") (name "SC4") (class "Default")
      (node (ref "C40") (pin "33") (pinfunction "33_33") (pintype "passive"))
      (node (ref "IC7") (pin "15") (pinfunction "QA_15") (pintype "tri_state"))
    )
    (net (code "145") (name "SDF0") (class "Default")
      (node (ref "A40") (pin "6") (pinfunction "6_6") (pintype "passive"))
      (node (ref "IC14") (pin "11") (pinfunction "A_11") (pintype "input"))
    )
    (net (code "146") (name "SDF1") (class "Default")
      (node (ref "A40") (pin "8") (pinfunction "8_8") (pintype "passive"))
      (node (ref "IC14") (pin "12") (pinfunction "B_12") (pintype "input"))
    )
    (net (code "147") (name "SDF2") (class "Default")
      (node (ref "A40") (pin "10") (pinfunction "10_10") (pintype "passive"))
      (node (ref "IC14") (pin "13") (pinfunction "C_13") (pintype "input"))
    )
    (net (code "148") (name "SI") (class "Default")
      (node (ref "B40") (pin "32") (pinfunction "32_32") (pintype "passive"))
      (node (ref "IC18") (pin "12") (pinfunction "B_12") (pintype "input"))
    )
    (net (code "149") (name "SIF0") (class "Default")
      (node (ref "A40") (pin "12") (pinfunction "12_12") (pintype "passive"))
      (node (ref "IC14") (pin "14") (pinfunction "D_14") (pintype "input"))
    )
    (net (code "150") (name "SIF1") (class "Default")
      (node (ref "A40") (pin "14") (pinfunction "14_14") (pintype "passive"))
      (node (ref "IC14") (pin "3") (pinfunction "E_3") (pintype "input"))
    )
    (net (code "151") (name "SIF2") (class "Default")
      (node (ref "A40") (pin "16") (pinfunction "16_16") (pintype "passive"))
      (node (ref "IC14") (pin "4") (pinfunction "F_4") (pintype "input"))
    )
    (net (code "152") (name "SR0") (class "Default")
      (node (ref "A40") (pin "18") (pinfunction "18_18") (pintype "passive"))
      (node (ref "IC14") (pin "5") (pinfunction "G_5") (pintype "input"))
    )
    (net (code "153") (name "SR1") (class "Default")
      (node (ref "A40") (pin "20") (pinfunction "20_20") (pintype "passive"))
      (node (ref "IC14") (pin "6") (pinfunction "H_6") (pintype "input"))
    )
    (net (code "154") (name "SR2") (class "Default")
      (node (ref "A40") (pin "26") (pinfunction "26_26") (pintype "passive"))
      (node (ref "IC15") (pin "11") (pinfunction "A_11") (pintype "input"))
    )
    (net (code "155") (name "SR3") (class "Default")
      (node (ref "A40") (pin "28") (pinfunction "28_28") (pintype "passive"))
      (node (ref "IC15") (pin "12") (pinfunction "B_12") (pintype "input"))
    )
    (net (code "156") (name "SR4") (class "Default")
      (node (ref "A40") (pin "30") (pinfunction "30_30") (pintype "passive"))
      (node (ref "IC15") (pin "13") (pinfunction "C_13") (pintype "input"))
    )
    (net (code "157") (name "SR5") (class "Default")
      (node (ref "A40") (pin "34") (pinfunction "34_34") (pintype "passive"))
      (node (ref "IC15") (pin "14") (pinfunction "D_14") (pintype "input"))
    )
    (net (code "158") (name "SR6") (class "Default")
      (node (ref "A40") (pin "32") (pinfunction "32_32") (pintype "passive"))
      (node (ref "IC15") (pin "3") (pinfunction "E_3") (pintype "input"))
    )
    (net (code "159") (name "SR7") (class "Default")
      (node (ref "B40") (pin "6") (pinfunction "6_6") (pintype "passive"))
      (node (ref "IC15") (pin "4") (pinfunction "F_4") (pintype "input"))
    )
    (net (code "160") (name "SR8") (class "Default")
      (node (ref "B40") (pin "8") (pinfunction "8_8") (pintype "passive"))
      (node (ref "IC15") (pin "5") (pinfunction "G_5") (pintype "input"))
    )
    (net (code "161") (name "SR9") (class "Default")
      (node (ref "B40") (pin "10") (pinfunction "10_10") (pintype "passive"))
      (node (ref "IC15") (pin "6") (pinfunction "H_6") (pintype "input"))
    )
    (net (code "162") (name "SR10") (class "Default")
      (node (ref "B40") (pin "12") (pinfunction "12_12") (pintype "passive"))
      (node (ref "IC16") (pin "11") (pinfunction "A_11") (pintype "input"))
    )
    (net (code "163") (name "SR11") (class "Default")
      (node (ref "B40") (pin "14") (pinfunction "14_14") (pintype "passive"))
      (node (ref "IC16") (pin "12") (pinfunction "B_12") (pintype "input"))
    )
    (net (code "164") (name "SS") (class "Default")
      (node (ref "B40") (pin "34") (pinfunction "34_34") (pintype "passive"))
      (node (ref "IC18") (pin "11") (pinfunction "A_11") (pintype "input"))
    )
    (net (code "165") (name "START") (class "Default")
      (node (ref "B40") (pin "16") (pinfunction "16_16") (pintype "passive"))
      (node (ref "IC16") (pin "13") (pinfunction "C_13") (pintype "input"))
    )
    (net (code "166") (name "STOP") (class "Default")
      (node (ref "B40") (pin "30") (pinfunction "30_30") (pintype "passive"))
      (node (ref "IC16") (pin "6") (pinfunction "H_6") (pintype "input"))
    )
    (net (code "167") (name "TAD") (class "Default")
      (node (ref "D40") (pin "4") (pinfunction "4_4") (pintype "passive"))
      (node (ref "IC10") (pin "5") (pinfunction "QF_5") (pintype "tri_state"))
    )
    (net (code "168") (name "VCC") (class "Default")
      (node (ref "C1") (pin "1") (pinfunction "1_1") (pintype "passive"))
      (node (ref "J2") (pin "2") (pinfunction "2_2") (pintype "passive"))
      (node (ref "R10") (pin "1") (pinfunction "1_1") (pintype "passive"))
      (node (ref "R6") (pin "1") (pinfunction "1_1") (pintype "passive"))
      (node (ref "R7") (pin "1") (pinfunction "1_1") (pintype "passive"))
      (node (ref "R8") (pin "1") (pinfunction "1_1") (pintype "passive"))
      (node (ref "R9") (pin "1") (pinfunction "1_1") (pintype "passive"))
      (node (ref "VCC1") (pin "1") (pinfunction "1_1") (pintype "passive"))
      (node (ref "VCC2") (pin "1") (pinfunction "1_1") (pintype "passive"))
      (node (ref "VCC3") (pin "1") (pinfunction "1_1") (pintype "passive"))
      (node (ref "VCC4") (pin "1") (pinfunction "1_1") (pintype "passive"))
    )
    (net (code "169") (name "VDD") (class "Default")
      (node (ref "3.3V") (pin "2") (pinfunction "2_2") (pintype "passive"))
      (node (ref "J4") (pin "4") (pinfunction "VDD_4") (pintype "power_in"))
    )
    (net (code "170") (name "VSS") (class "Default")
      (node (ref "J3") (pin "1") (pinfunction "1_1") (pintype "passive"))
      (node (ref "J4") (pin "3") (pinfunction "VSS_3") (pintype "power_in"))
      (node (ref "J4") (pin "6") (pinfunction "VSS_6") (pintype "power_in"))
    )
    (net (code "171") (name "WC") (class "Default")
      (node (ref "D40") (pin "30") (pinfunction "30_30") (pintype "passive"))
      (node (ref "IC11") (pin "7") (pinfunction "QH_7") (pintype "tri_state"))
    )
    (net (code "172") (name "unconnected-(A40-Pad1)") (class "Default")
      (node (ref "A40") (pin "1") (pinfunction "1_1") (pintype "passive"))
    )
    (net (code "173") (name "unconnected-(A40-Pad2)") (class "Default")
      (node (ref "A40") (pin "2") (pinfunction "2_2") (pintype "passive"))
    )
    (net (code "174") (name "unconnected-(A40-Pad3)") (class "Default")
      (node (ref "A40") (pin "3") (pinfunction "3_3") (pintype "passive"))
    )
    (net (code "175") (name "unconnected-(A40-Pad5)") (class "Default")
      (node (ref "A40") (pin "5") (pinfunction "5_5") (pintype "passive"))
    )
    (net (code "176") (name "unconnected-(A40-Pad7)") (class "Default")
      (node (ref "A40") (pin "7") (pinfunction "7_7") (pintype "passive"))
    )
    (net (code "177") (name "unconnected-(A40-Pad9)") (class "Default")
      (node (ref "A40") (pin "9") (pinfunction "9_9") (pintype "passive"))
    )
    (net (code "178") (name "unconnected-(A40-Pad11)") (class "Default")
      (node (ref "A40") (pin "11") (pinfunction "11_11") (pintype "passive"))
    )
    (net (code "179") (name "unconnected-(A40-Pad13)") (class "Default")
      (node (ref "A40") (pin "13") (pinfunction "13_13") (pintype "passive"))
    )
    (net (code "180") (name "unconnected-(A40-Pad15)") (class "Default")
      (node (ref "A40") (pin "15") (pinfunction "15_15") (pintype "passive"))
    )
    (net (code "181") (name "unconnected-(A40-Pad17)") (class "Default")
      (node (ref "A40") (pin "17") (pinfunction "17_17") (pintype "passive"))
    )
    (net (code "182") (name "unconnected-(A40-Pad19)") (class "Default")
      (node (ref "A40") (pin "19") (pinfunction "19_19") (pintype "passive"))
    )
    (net (code "183") (name "unconnected-(A40-Pad21)") (class "Default")
      (node (ref "A40") (pin "21") (pinfunction "21_21") (pintype "passive"))
    )
    (net (code "184") (name "unconnected-(A40-Pad22)") (class "Default")
      (node (ref "A40") (pin "22") (pinfunction "22_22") (pintype "passive"))
    )
    (net (code "185") (name "unconnected-(A40-Pad23)") (class "Default")
      (node (ref "A40") (pin "23") (pinfunction "23_23") (pintype "passive"))
    )
    (net (code "186") (name "unconnected-(A40-Pad24)") (class "Default")
      (node (ref "A40") (pin "24") (pinfunction "24_24") (pintype "passive"))
    )
    (net (code "187") (name "unconnected-(A40-Pad25)") (class "Default")
      (node (ref "A40") (pin "25") (pinfunction "25_25") (pintype "passive"))
    )
    (net (code "188") (name "unconnected-(A40-Pad27)") (class "Default")
      (node (ref "A40") (pin "27") (pinfunction "27_27") (pintype "passive"))
    )
    (net (code "189") (name "unconnected-(A40-Pad29)") (class "Default")
      (node (ref "A40") (pin "29") (pinfunction "29_29") (pintype "passive"))
    )
    (net (code "190") (name "unconnected-(A40-Pad31)") (class "Default")
      (node (ref "A40") (pin "31") (pinfunction "31_31") (pintype "passive"))
    )
    (net (code "191") (name "unconnected-(A40-Pad33)") (class "Default")
      (node (ref "A40") (pin "33") (pinfunction "33_33") (pintype "passive"))
    )
    (net (code "192") (name "unconnected-(B40-Pad1)") (class "Default")
      (node (ref "B40") (pin "1") (pinfunction "1_1") (pintype "passive"))
    )
    (net (code "193") (name "unconnected-(B40-Pad2)") (class "Default")
      (node (ref "B40") (pin "2") (pinfunction "2_2") (pintype "passive"))
    )
    (net (code "194") (name "unconnected-(B40-Pad3)") (class "Default")
      (node (ref "B40") (pin "3") (pinfunction "3_3") (pintype "passive"))
    )
    (net (code "195") (name "unconnected-(B40-Pad5)") (class "Default")
      (node (ref "B40") (pin "5") (pinfunction "5_5") (pintype "passive"))
    )
    (net (code "196") (name "unconnected-(B40-Pad7)") (class "Default")
      (node (ref "B40") (pin "7") (pinfunction "7_7") (pintype "passive"))
    )
    (net (code "197") (name "unconnected-(B40-Pad9)") (class "Default")
      (node (ref "B40") (pin "9") (pinfunction "9_9") (pintype "passive"))
    )
    (net (code "198") (name "unconnected-(B40-Pad11)") (class "Default")
      (node (ref "B40") (pin "11") (pinfunction "11_11") (pintype "passive"))
    )
    (net (code "199") (name "unconnected-(B40-Pad13)") (class "Default")
      (node (ref "B40") (pin "13") (pinfunction "13_13") (pintype "passive"))
    )
    (net (code "200") (name "unconnected-(B40-Pad15)") (class "Default")
      (node (ref "B40") (pin "15") (pinfunction "15_15") (pintype "passive"))
    )
    (net (code "201") (name "unconnected-(B40-Pad17)") (class "Default")
      (node (ref "B40") (pin "17") (pinfunction "17_17") (pintype "passive"))
    )
    (net (code "202") (name "unconnected-(B40-Pad19)") (class "Default")
      (node (ref "B40") (pin "19") (pinfunction "19_19") (pintype "passive"))
    )
    (net (code "203") (name "unconnected-(B40-Pad21)") (class "Default")
      (node (ref "B40") (pin "21") (pinfunction "21_21") (pintype "passive"))
    )
    (net (code "204") (name "unconnected-(B40-Pad22)") (class "Default")
      (node (ref "B40") (pin "22") (pinfunction "22_22") (pintype "passive"))
    )
    (net (code "205") (name "unconnected-(B40-Pad23)") (class "Default")
      (node (ref "B40") (pin "23") (pinfunction "23_23") (pintype "passive"))
    )
    (net (code "206") (name "unconnected-(B40-Pad24)") (class "Default")
      (node (ref "B40") (pin "24") (pinfunction "24_24") (pintype "passive"))
    )
    (net (code "207") (name "unconnected-(B40-Pad25)") (class "Default")
      (node (ref "B40") (pin "25") (pinfunction "25_25") (pintype "passive"))
    )
    (net (code "208") (name "unconnected-(B40-Pad27)") (class "Default")
      (node (ref "B40") (pin "27") (pinfunction "27_27") (pintype "passive"))
    )
    (net (code "209") (name "unconnected-(B40-Pad29)") (class "Default")
      (node (ref "B40") (pin "29") (pinfunction "29_29") (pintype "passive"))
    )
    (net (code "210") (name "unconnected-(B40-Pad31)") (class "Default")
      (node (ref "B40") (pin "31") (pinfunction "31_31") (pintype "passive"))
    )
    (net (code "211") (name "unconnected-(B40-Pad33)") (class "Default")
      (node (ref "B40") (pin "33") (pinfunction "33_33") (pintype "passive"))
    )
    (net (code "212") (name "unconnected-(C40-Pad3)") (class "Default")
      (node (ref "C40") (pin "3") (pinfunction "3_3") (pintype "passive"))
    )
    (net (code "213") (name "unconnected-(C40-Pad4)") (class "Default")
      (node (ref "C40") (pin "4") (pinfunction "4_4") (pintype "passive"))
    )
    (net (code "214") (name "unconnected-(C40-Pad5)") (class "Default")
      (node (ref "C40") (pin "5") (pinfunction "5_5") (pintype "passive"))
    )
    (net (code "215") (name "unconnected-(C40-Pad6)") (class "Default")
      (node (ref "C40") (pin "6") (pinfunction "6_6") (pintype "passive"))
    )
    (net (code "216") (name "unconnected-(C40-Pad7)") (class "Default")
      (node (ref "C40") (pin "7") (pinfunction "7_7") (pintype "passive"))
    )
    (net (code "217") (name "unconnected-(C40-Pad8)") (class "Default")
      (node (ref "C40") (pin "8") (pinfunction "8_8") (pintype "passive"))
    )
    (net (code "218") (name "unconnected-(C40-Pad13)") (class "Default")
      (node (ref "C40") (pin "13") (pinfunction "13_13") (pintype "passive"))
    )
    (net (code "219") (name "unconnected-(C40-Pad14)") (class "Default")
      (node (ref "C40") (pin "14") (pinfunction "14_14") (pintype "passive"))
    )
    (net (code "220") (name "unconnected-(C40-Pad15)") (class "Default")
      (node (ref "C40") (pin "15") (pinfunction "15_15") (pintype "passive"))
    )
    (net (code "221") (name "unconnected-(C40-Pad16)") (class "Default")
      (node (ref "C40") (pin "16") (pinfunction "16_16") (pintype "passive"))
    )
    (net (code "222") (name "unconnected-(C40-Pad21)") (class "Default")
      (node (ref "C40") (pin "21") (pinfunction "21_21") (pintype "passive"))
    )
    (net (code "223") (name "unconnected-(C40-Pad22)") (class "Default")
      (node (ref "C40") (pin "22") (pinfunction "22_22") (pintype "passive"))
    )
    (net (code "224") (name "unconnected-(C40-Pad26)") (class "Default")
      (node (ref "C40") (pin "26") (pinfunction "26_26") (pintype "passive"))
    )
    (net (code "225") (name "unconnected-(C40-Pad27)") (class "Default")
      (node (ref "C40") (pin "27") (pinfunction "27_27") (pintype "passive"))
    )
    (net (code "226") (name "unconnected-(C40-Pad29)") (class "Default")
      (node (ref "C40") (pin "29") (pinfunction "29_29") (pintype "passive"))
    )
    (net (code "227") (name "unconnected-(C40-Pad30)") (class "Default")
      (node (ref "C40") (pin "30") (pinfunction "30_30") (pintype "passive"))
    )
    (net (code "228") (name "unconnected-(C40-Pad31)") (class "Default")
      (node (ref "C40") (pin "31") (pinfunction "31_31") (pintype "passive"))
    )
    (net (code "229") (name "unconnected-(C40-Pad32)") (class "Default")
      (node (ref "C40") (pin "32") (pinfunction "32_32") (pintype "passive"))
    )
    (net (code "230") (name "unconnected-(D40-Pad1)") (class "Default")
      (node (ref "D40") (pin "1") (pinfunction "1_1") (pintype "passive"))
    )
    (net (code "231") (name "unconnected-(D40-Pad3)") (class "Default")
      (node (ref "D40") (pin "3") (pinfunction "3_3") (pintype "passive"))
    )
    (net (code "232") (name "unconnected-(D40-Pad5)") (class "Default")
      (node (ref "D40") (pin "5") (pinfunction "5_5") (pintype "passive"))
    )
    (net (code "233") (name "unconnected-(D40-Pad7)") (class "Default")
      (node (ref "D40") (pin "7") (pinfunction "7_7") (pintype "passive"))
    )
    (net (code "234") (name "unconnected-(D40-Pad9)") (class "Default")
      (node (ref "D40") (pin "9") (pinfunction "9_9") (pintype "passive"))
    )
    (net (code "235") (name "unconnected-(D40-Pad11)") (class "Default")
      (node (ref "D40") (pin "11") (pinfunction "11_11") (pintype "passive"))
    )
    (net (code "236") (name "unconnected-(D40-Pad13)") (class "Default")
      (node (ref "D40") (pin "13") (pinfunction "13_13") (pintype "passive"))
    )
    (net (code "237") (name "unconnected-(D40-Pad14)") (class "Default")
      (node (ref "D40") (pin "14") (pinfunction "14_14") (pintype "passive"))
    )
    (net (code "238") (name "unconnected-(D40-Pad15)") (class "Default")
      (node (ref "D40") (pin "15") (pinfunction "15_15") (pintype "passive"))
    )
    (net (code "239") (name "unconnected-(D40-Pad21)") (class "Default")
      (node (ref "D40") (pin "21") (pinfunction "21_21") (pintype "passive"))
    )
    (net (code "240") (name "unconnected-(D40-Pad25)") (class "Default")
      (node (ref "D40") (pin "25") (pinfunction "25_25") (pintype "passive"))
    )
    (net (code "241") (name "unconnected-(D40-Pad27)") (class "Default")
      (node (ref "D40") (pin "27") (pinfunction "27_27") (pintype "passive"))
    )
    (net (code "242") (name "unconnected-(D40-Pad29)") (class "Default")
      (node (ref "D40") (pin "29") (pinfunction "29_29") (pintype "passive"))
    )
    (net (code "243") (name "unconnected-(IC4A-QG-Pad6)") (class "Default")
      (node (ref "IC4") (pin "6") (pinfunction "QG_6") (pintype "tri_state"))
    )
    (net (code "244") (name "unconnected-(IC4A-QH-Pad7)") (class "Default")
      (node (ref "IC4") (pin "7") (pinfunction "QH_7") (pintype "tri_state"))
    )
    (net (code "245") (name "unconnected-(IC8A-QG-Pad6)") (class "Default")
      (node (ref "IC8") (pin "6") (pinfunction "QG_6") (pintype "tri_state"))
    )
    (net (code "246") (name "unconnected-(IC8A-QH-Pad7)") (class "Default")
      (node (ref "IC8") (pin "7") (pinfunction "QH_7") (pintype "tri_state"))
    )
    (net (code "247") (name "unconnected-(IC12A-QF-Pad5)") (class "Default")
      (node (ref "IC12") (pin "5") (pinfunction "QF_5") (pintype "tri_state"))
    )
    (net (code "248") (name "unconnected-(IC12A-QG-Pad6)") (class "Default")
      (node (ref "IC12") (pin "6") (pinfunction "QG_6") (pintype "tri_state"))
    )
    (net (code "249") (name "unconnected-(IC12A-QH-Pad7)") (class "Default")
      (node (ref "IC12") (pin "7") (pinfunction "QH_7") (pintype "tri_state"))
    )
    (net (code "250") (name "unconnected-(IC13A-R1OUT-Pad12)") (class "Default")
      (node (ref "IC13") (pin "12") (pinfunction "R1OUT_12") (pintype "output"))
    )
    (net (code "251") (name "unconnected-(IC14A-~{QH}-Pad7)") (class "Default")
      (node (ref "IC14") (pin "7") (pinfunction "~{QH}_7") (pintype "output"))
    )
    (net (code "252") (name "unconnected-(IC15A-~{QH}-Pad7)") (class "Default")
      (node (ref "IC15") (pin "7") (pinfunction "~{QH}_7") (pintype "output"))
    )
    (net (code "253") (name "unconnected-(IC16A-~{QH}-Pad7)") (class "Default")
      (node (ref "IC16") (pin "7") (pinfunction "~{QH}_7") (pintype "output"))
    )
    (net (code "254") (name "unconnected-(IC18A-~{QH}-Pad7)") (class "Default")
      (node (ref "IC18") (pin "7") (pinfunction "~{QH}_7") (pintype "output"))
    )
    (net (code "255") (name "unconnected-(XESS-BSY-Pad17)") (class "Default")
      (node (ref "XESS") (pin "17") (pinfunction "BSY_17") (pintype "bidirectional"))
    )
    (net (code "256") (name "unconnected-(XESS-CLKB-Pad11)") (class "Default")
      (node (ref "XESS") (pin "11") (pinfunction "CLKB_11") (pintype "bidirectional"))
    )
    (net (code "257") (name "unconnected-(XESS-CLKC-Pad64)") (class "Default")
      (node (ref "XESS") (pin "64") (pinfunction "CLKC_64") (pintype "bidirectional"))
    )
    (net (code "258") (name "unconnected-(XESS-CS#-Pad15)") (class "Default")
      (node (ref "XESS") (pin "15") (pinfunction "CS#_15") (pintype "bidirectional"))
    )
    (net (code "259") (name "unconnected-(XESS-D1-Pad25)") (class "Default")
      (node (ref "XESS") (pin "25") (pinfunction "D1_25") (pintype "bidirectional"))
    )
    (net (code "260") (name "unconnected-(XESS-D2-Pad24)") (class "Default")
      (node (ref "XESS") (pin "24") (pinfunction "D2_24") (pintype "bidirectional"))
    )
    (net (code "261") (name "unconnected-(XESS-D15-Pad21)") (class "Default")
      (node (ref "XESS") (pin "21") (pinfunction "D15_21") (pintype "bidirectional"))
    )
    (net (code "262") (name "unconnected-(XESS-D16-Pad19)") (class "Default")
      (node (ref "XESS") (pin "19") (pinfunction "D16_19") (pintype "bidirectional"))
    )
    (net (code "263") (name "unconnected-(XESS-E14-Pad20)") (class "Default")
      (node (ref "XESS") (pin "20") (pinfunction "E14_20") (pintype "bidirectional"))
    )
    (net (code "264") (name "unconnected-(XESS-E15-Pad18)") (class "Default")
      (node (ref "XESS") (pin "18") (pinfunction "E15_18") (pintype "bidirectional"))
    )
    (net (code "265") (name "unconnected-(XESS-E16-Pad14)") (class "Default")
      (node (ref "XESS") (pin "14") (pinfunction "E16_14") (pintype "bidirectional"))
    )
    (net (code "266") (name "unconnected-(XESS-F5-Pad23)") (class "Default")
      (node (ref "XESS") (pin "23") (pinfunction "F5_23") (pintype "bidirectional"))
    )
    (net (code "267") (name "unconnected-(XESS-F14-Pad13)") (class "Default")
      (node (ref "XESS") (pin "13") (pinfunction "F14_13") (pintype "bidirectional"))
    )
    (net (code "268") (name "unconnected-(XESS-G1-Pad36)") (class "Default")
      (node (ref "XESS") (pin "36") (pinfunction "G1_36") (pintype "bidirectional"))
    )
    (net (code "269") (name "unconnected-(XESS-G3-Pad34)") (class "Default")
      (node (ref "XESS") (pin "34") (pinfunction "G3_34") (pintype "bidirectional"))
    )
    (net (code "270") (name "unconnected-(XESS-G12-Pad12)") (class "Default")
      (node (ref "XESS") (pin "12") (pinfunction "G12_12") (pintype "bidirectional"))
    )
    (net (code "271") (name "unconnected-(XESS-G13-Pad9)") (class "Default")
      (node (ref "XESS") (pin "9") (pinfunction "G13_9") (pintype "bidirectional"))
    )
    (net (code "272") (name "unconnected-(XESS-G14-Pad8)") (class "Default")
      (node (ref "XESS") (pin "8") (pinfunction "G14_8") (pintype "bidirectional"))
    )
    (net (code "273") (name "unconnected-(XESS-G15-Pad7)") (class "Default")
      (node (ref "XESS") (pin "7") (pinfunction "G15_7") (pintype "bidirectional"))
    )
    (net (code "274") (name "unconnected-(XESS-G16-Pad6)") (class "Default")
      (node (ref "XESS") (pin "6") (pinfunction "G16_6") (pintype "bidirectional"))
    )
    (net (code "275") (name "unconnected-(XESS-H4-Pad37)") (class "Default")
      (node (ref "XESS") (pin "37") (pinfunction "H4_37") (pintype "bidirectional"))
    )
    (net (code "276") (name "unconnected-(XESS-H13-Pad5)") (class "Default")
      (node (ref "XESS") (pin "5") (pinfunction "H13_5") (pintype "bidirectional"))
    )
    (net (code "277") (name "unconnected-(XESS-H14-Pad4)") (class "Default")
      (node (ref "XESS") (pin "4") (pinfunction "H14_4") (pintype "bidirectional"))
    )
    (net (code "278") (name "unconnected-(XESS-H15-Pad3)") (class "Default")
      (node (ref "XESS") (pin "3") (pinfunction "H15_3") (pintype "bidirectional"))
    )
    (net (code "279") (name "unconnected-(XESS-H16-Pad1)") (class "Default")
      (node (ref "XESS") (pin "1") (pinfunction "H16_1") (pintype "bidirectional"))
    )
    (net (code "280") (name "unconnected-(XESS-J3-Pad42)") (class "Default")
      (node (ref "XESS") (pin "42") (pinfunction "J3_42") (pintype "bidirectional"))
    )
    (net (code "281") (name "unconnected-(XESS-J13-Pad82)") (class "Default")
      (node (ref "XESS") (pin "82") (pinfunction "J13_82") (pintype "bidirectional"))
    )
    (net (code "282") (name "unconnected-(XESS-J14-Pad83)") (class "Default")
      (node (ref "XESS") (pin "83") (pinfunction "J14_83") (pintype "bidirectional"))
    )
    (net (code "283") (name "unconnected-(XESS-J16-Pad84)") (class "Default")
      (node (ref "XESS") (pin "84") (pinfunction "J16_84") (pintype "bidirectional"))
    )
    (net (code "284") (name "unconnected-(XESS-K1-Pad43)") (class "Default")
      (node (ref "XESS") (pin "43") (pinfunction "K1_43") (pintype "bidirectional"))
    )
    (net (code "285") (name "unconnected-(XESS-K5-Pad45)") (class "Default")
      (node (ref "XESS") (pin "45") (pinfunction "K5_45") (pintype "bidirectional"))
    )
    (net (code "286") (name "unconnected-(XESS-L2-Pad44)") (class "Default")
      (node (ref "XESS") (pin "44") (pinfunction "L2_44") (pintype "bidirectional"))
    )
    (net (code "287") (name "unconnected-(XESS-L3-Pad46)") (class "Default")
      (node (ref "XESS") (pin "46") (pinfunction "L3_46") (pintype "bidirectional"))
    )
    (net (code "288") (name "unconnected-(XESS-L4-Pad49)") (class "Default")
      (node (ref "XESS") (pin "49") (pinfunction "L4_49") (pintype "bidirectional"))
    )
    (net (code "289") (name "unconnected-(XESS-L5-Pad57)") (class "Default")
      (node (ref "XESS") (pin "57") (pinfunction "L5_57") (pintype "bidirectional"))
    )
    (net (code "290") (name "unconnected-(XESS-L15-Pad79)") (class "Default")
      (node (ref "XESS") (pin "79") (pinfunction "L15_79") (pintype "bidirectional"))
    )
    (net (code "291") (name "unconnected-(XESS-M1-Pad47)") (class "Default")
      (node (ref "XESS") (pin "47") (pinfunction "M1_47") (pintype "bidirectional"))
    )
    (net (code "292") (name "unconnected-(XESS-M2-Pad48)") (class "Default")
      (node (ref "XESS") (pin "48") (pinfunction "M2_48") (pintype "bidirectional"))
    )
    (net (code "293") (name "unconnected-(XESS-M3-Pad51)") (class "Default")
      (node (ref "XESS") (pin "51") (pinfunction "M3_51") (pintype "bidirectional"))
    )
    (net (code "294") (name "unconnected-(XESS-M4-Pad59)") (class "Default")
      (node (ref "XESS") (pin "59") (pinfunction "M4_59") (pintype "bidirectional"))
    )
    (net (code "295") (name "unconnected-(XESS-M10-Pad66)") (class "Default")
      (node (ref "XESS") (pin "66") (pinfunction "M10_66") (pintype "bidirectional"))
    )
    (net (code "296") (name "unconnected-(XESS-M15-Pad78)") (class "Default")
      (node (ref "XESS") (pin "78") (pinfunction "M15_78") (pintype "bidirectional"))
    )
    (net (code "297") (name "unconnected-(XESS-N1-Pad50)") (class "Default")
      (node (ref "XESS") (pin "50") (pinfunction "N1_50") (pintype "bidirectional"))
    )
    (net (code "298") (name "unconnected-(XESS-N2-Pad56)") (class "Default")
      (node (ref "XESS") (pin "56") (pinfunction "N2_56") (pintype "bidirectional"))
    )
    (net (code "299") (name "unconnected-(XESS-N3-Pad60)") (class "Default")
      (node (ref "XESS") (pin "60") (pinfunction "N3_60") (pintype "bidirectional"))
    )
    (net (code "300") (name "unconnected-(XESS-N15-Pad77)") (class "Default")
      (node (ref "XESS") (pin "77") (pinfunction "N15_77") (pintype "bidirectional"))
    )
    (net (code "301") (name "unconnected-(XESS-P$53-Pad53)") (class "Default")
      (node (ref "XESS") (pin "53") (pinfunction "P$53_53") (pintype "bidirectional"))
    )
    (net (code "302") (name "unconnected-(XESS-P$63-Pad63)") (class "Default")
      (node (ref "XESS") (pin "63") (pinfunction "P$63_63") (pintype "bidirectional"))
    )
    (net (code "303") (name "unconnected-(XESS-P$65-Pad65)") (class "Default")
      (node (ref "XESS") (pin "65") (pinfunction "P$65_65") (pintype "bidirectional"))
    )
    (net (code "304") (name "unconnected-(XESS-P$72-Pad72)") (class "Default")
      (node (ref "XESS") (pin "72") (pinfunction "P$72_72") (pintype "bidirectional"))
    )
    (net (code "305") (name "unconnected-(XESS-P$73-Pad73)") (class "Default")
      (node (ref "XESS") (pin "73") (pinfunction "P$73_73") (pintype "bidirectional"))
    )
    (net (code "306") (name "unconnected-(XESS-P$74-Pad74)") (class "Default")
      (node (ref "XESS") (pin "74") (pinfunction "P$74_74") (pintype "bidirectional"))
    )
    (net (code "307") (name "unconnected-(XESS-P$75-Pad75)") (class "Default")
      (node (ref "XESS") (pin "75") (pinfunction "P$75_75") (pintype "bidirectional"))
    )
    (net (code "308") (name "unconnected-(XESS-P$76-Pad76)") (class "Default")
      (node (ref "XESS") (pin "76") (pinfunction "P$76_76") (pintype "bidirectional"))
    )
    (net (code "309") (name "unconnected-(XESS-P1-Pad58)") (class "Default")
      (node (ref "XESS") (pin "58") (pinfunction "P1_58") (pintype "bidirectional"))
    )
    (net (code "310") (name "unconnected-(XESS-P2-Pad61)") (class "Default")
      (node (ref "XESS") (pin "61") (pinfunction "P2_61") (pintype "bidirectional"))
    )
    (net (code "311") (name "unconnected-(XESS-P11-Pad67)") (class "Default")
      (node (ref "XESS") (pin "67") (pinfunction "P11_67") (pintype "bidirectional"))
    )
    (net (code "312") (name "unconnected-(XESS-PROG#-Pad55)") (class "Default")
      (node (ref "XESS") (pin "55") (pinfunction "PROG#_55") (pintype "bidirectional"))
    )
    (net (code "313") (name "unconnected-(XESS-R1-Pad62)") (class "Default")
      (node (ref "XESS") (pin "62") (pinfunction "R1_62") (pintype "bidirectional"))
    )
    (net (code "314") (name "unconnected-(XESS-R12-Pad69)") (class "Default")
      (node (ref "XESS") (pin "69") (pinfunction "R12_69") (pintype "bidirectional"))
    )
    (net (code "315") (name "unconnected-(XESS-T12-Pad68)") (class "Default")
      (node (ref "XESS") (pin "68") (pinfunction "T12_68") (pintype "bidirectional"))
    )
    (net (code "316") (name "unconnected-(XESS-T13-Pad70)") (class "Default")
      (node (ref "XESS") (pin "70") (pinfunction "T13_70") (pintype "bidirectional"))
    )
    (net (code "317") (name "unconnected-(XESS-TCK-Pad16)") (class "Default")
      (node (ref "XESS") (pin "16") (pinfunction "TCK_16") (pintype "bidirectional"))
    )
    (net (code "318") (name "unconnected-(XESS-WR#-Pad30)") (class "Default")
      (node (ref "XESS") (pin "30") (pinfunction "WR#_30") (pintype "bidirectional"))
    )
  )
)
